# Core_Board_FPGA_STM32.net
KiCad netlist of a schematic drawn in Altium Designer
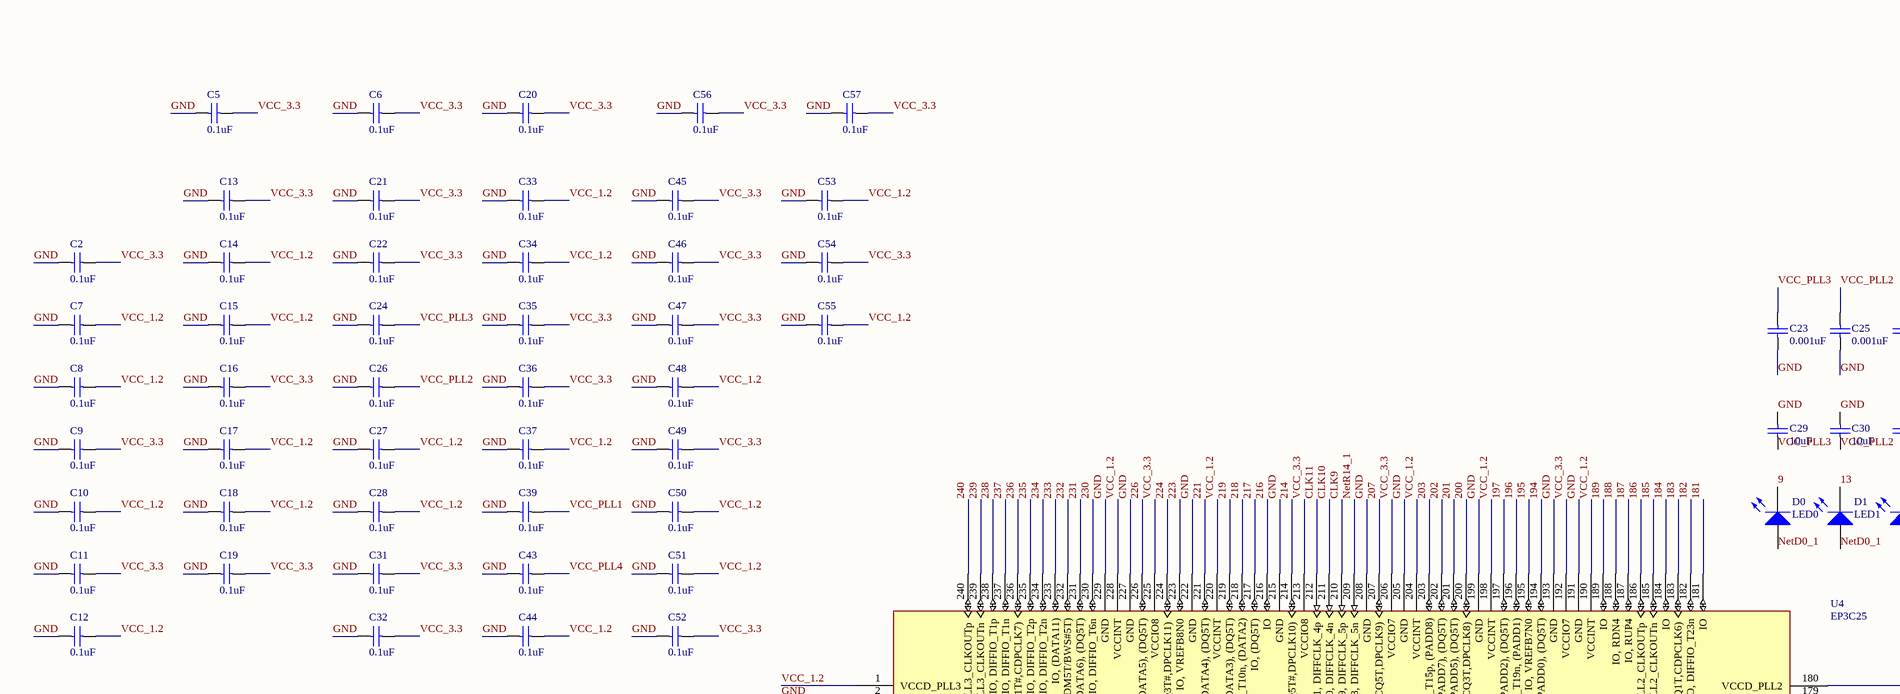
[diagram p0: Core_Board_FPGA_STM32.SchDoc, top left]
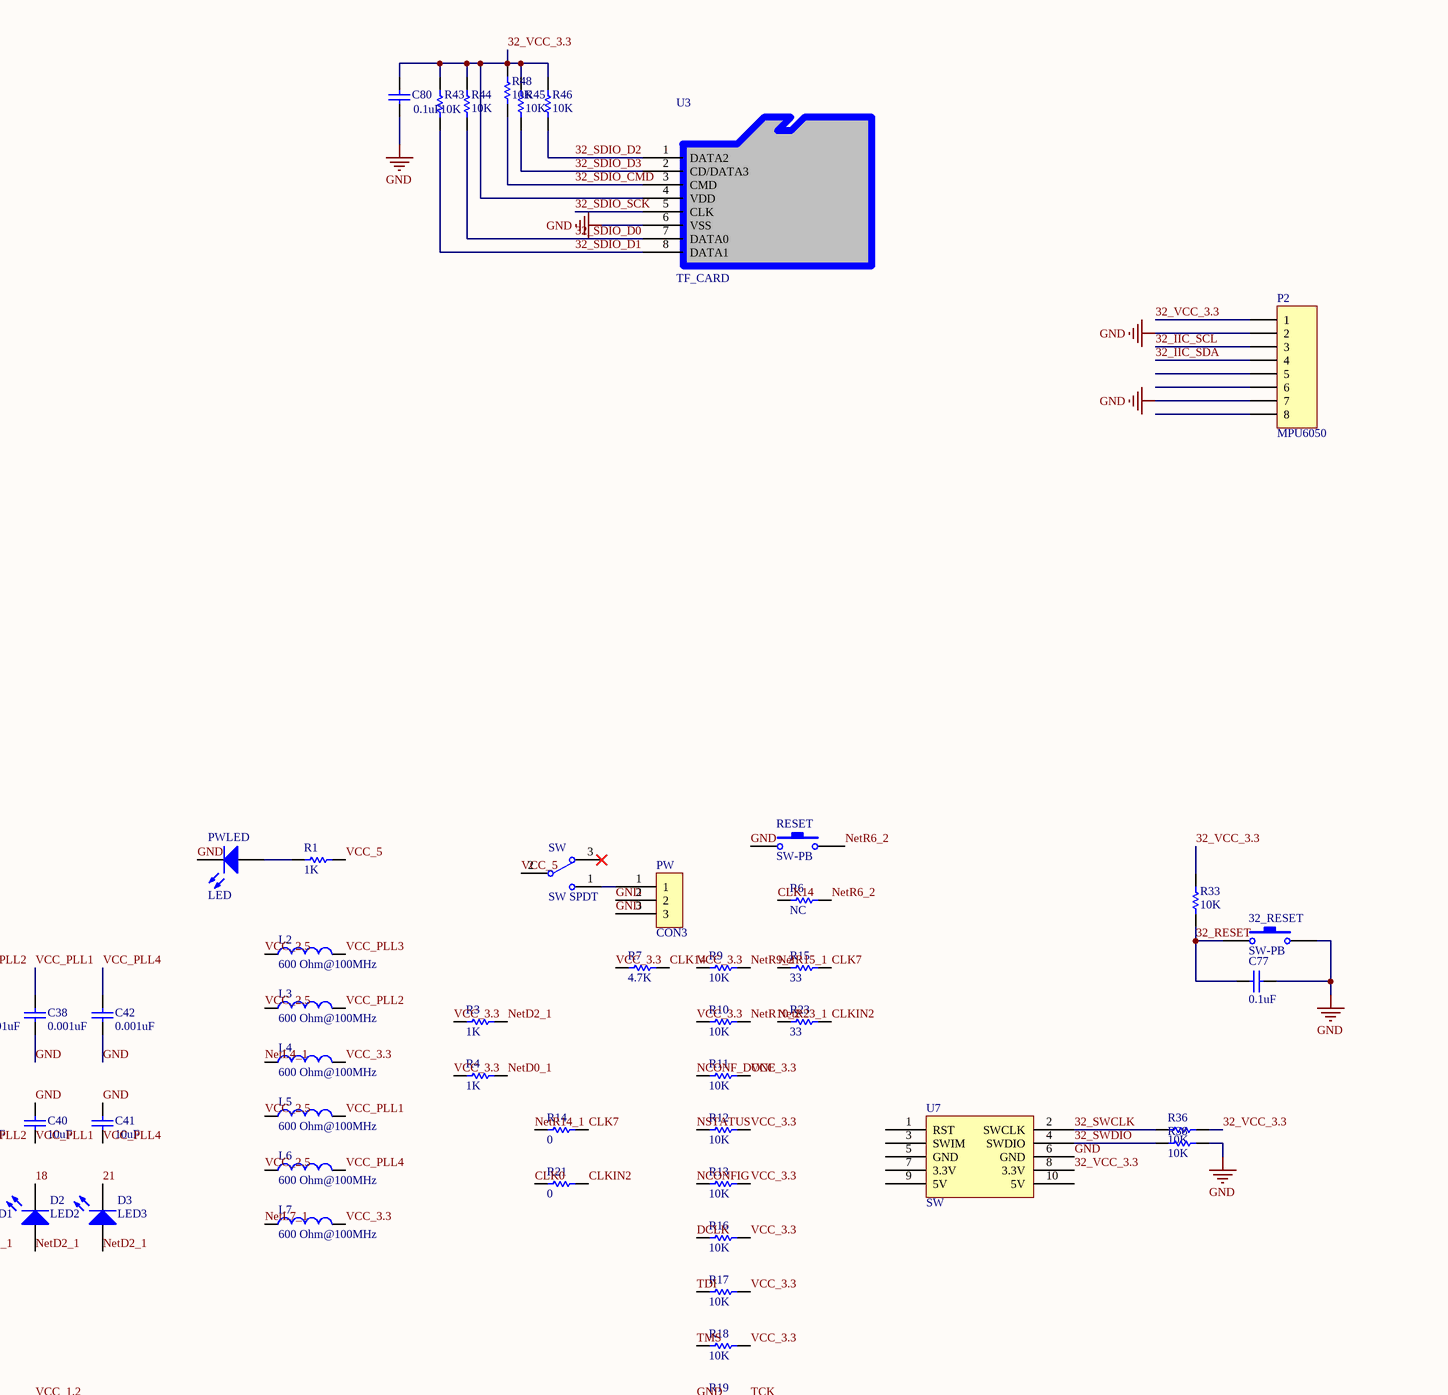
[diagram p1: Core_Board_FPGA_STM32.SchDoc, top middle]
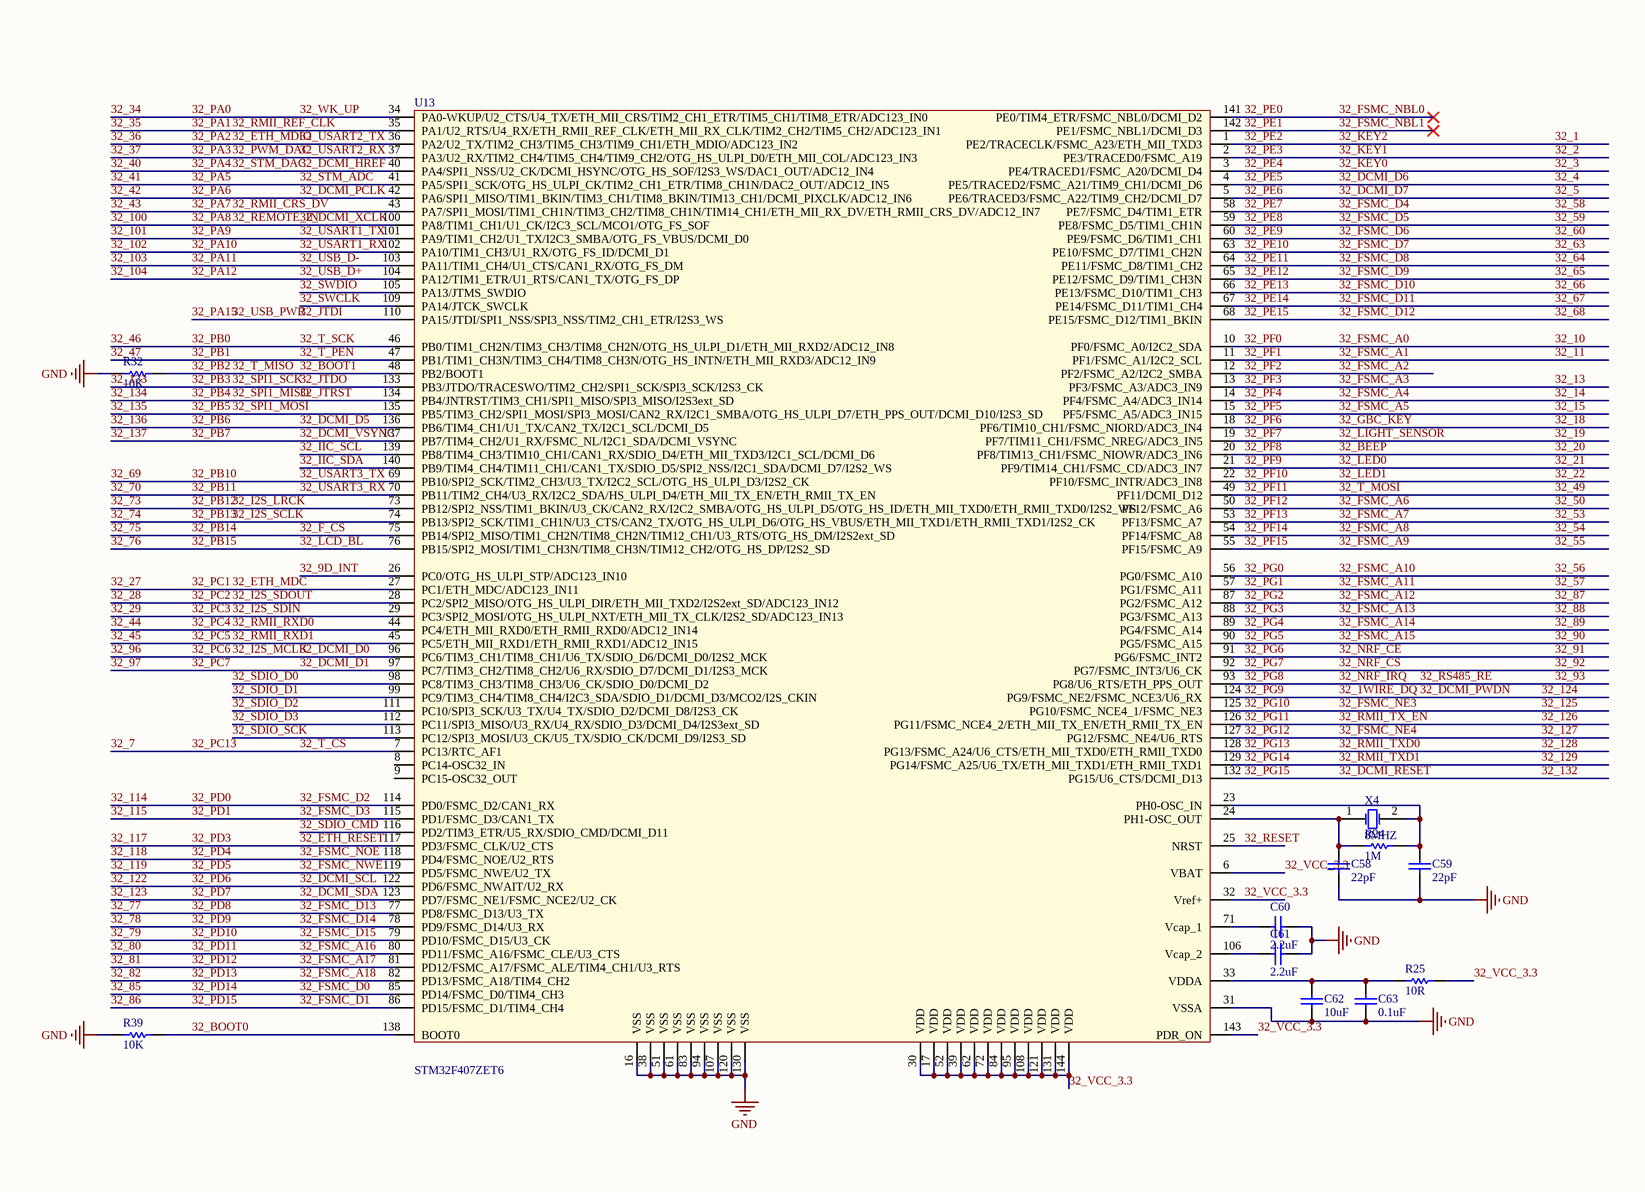
[diagram p2: Core_Board_FPGA_STM32.SchDoc, top right]
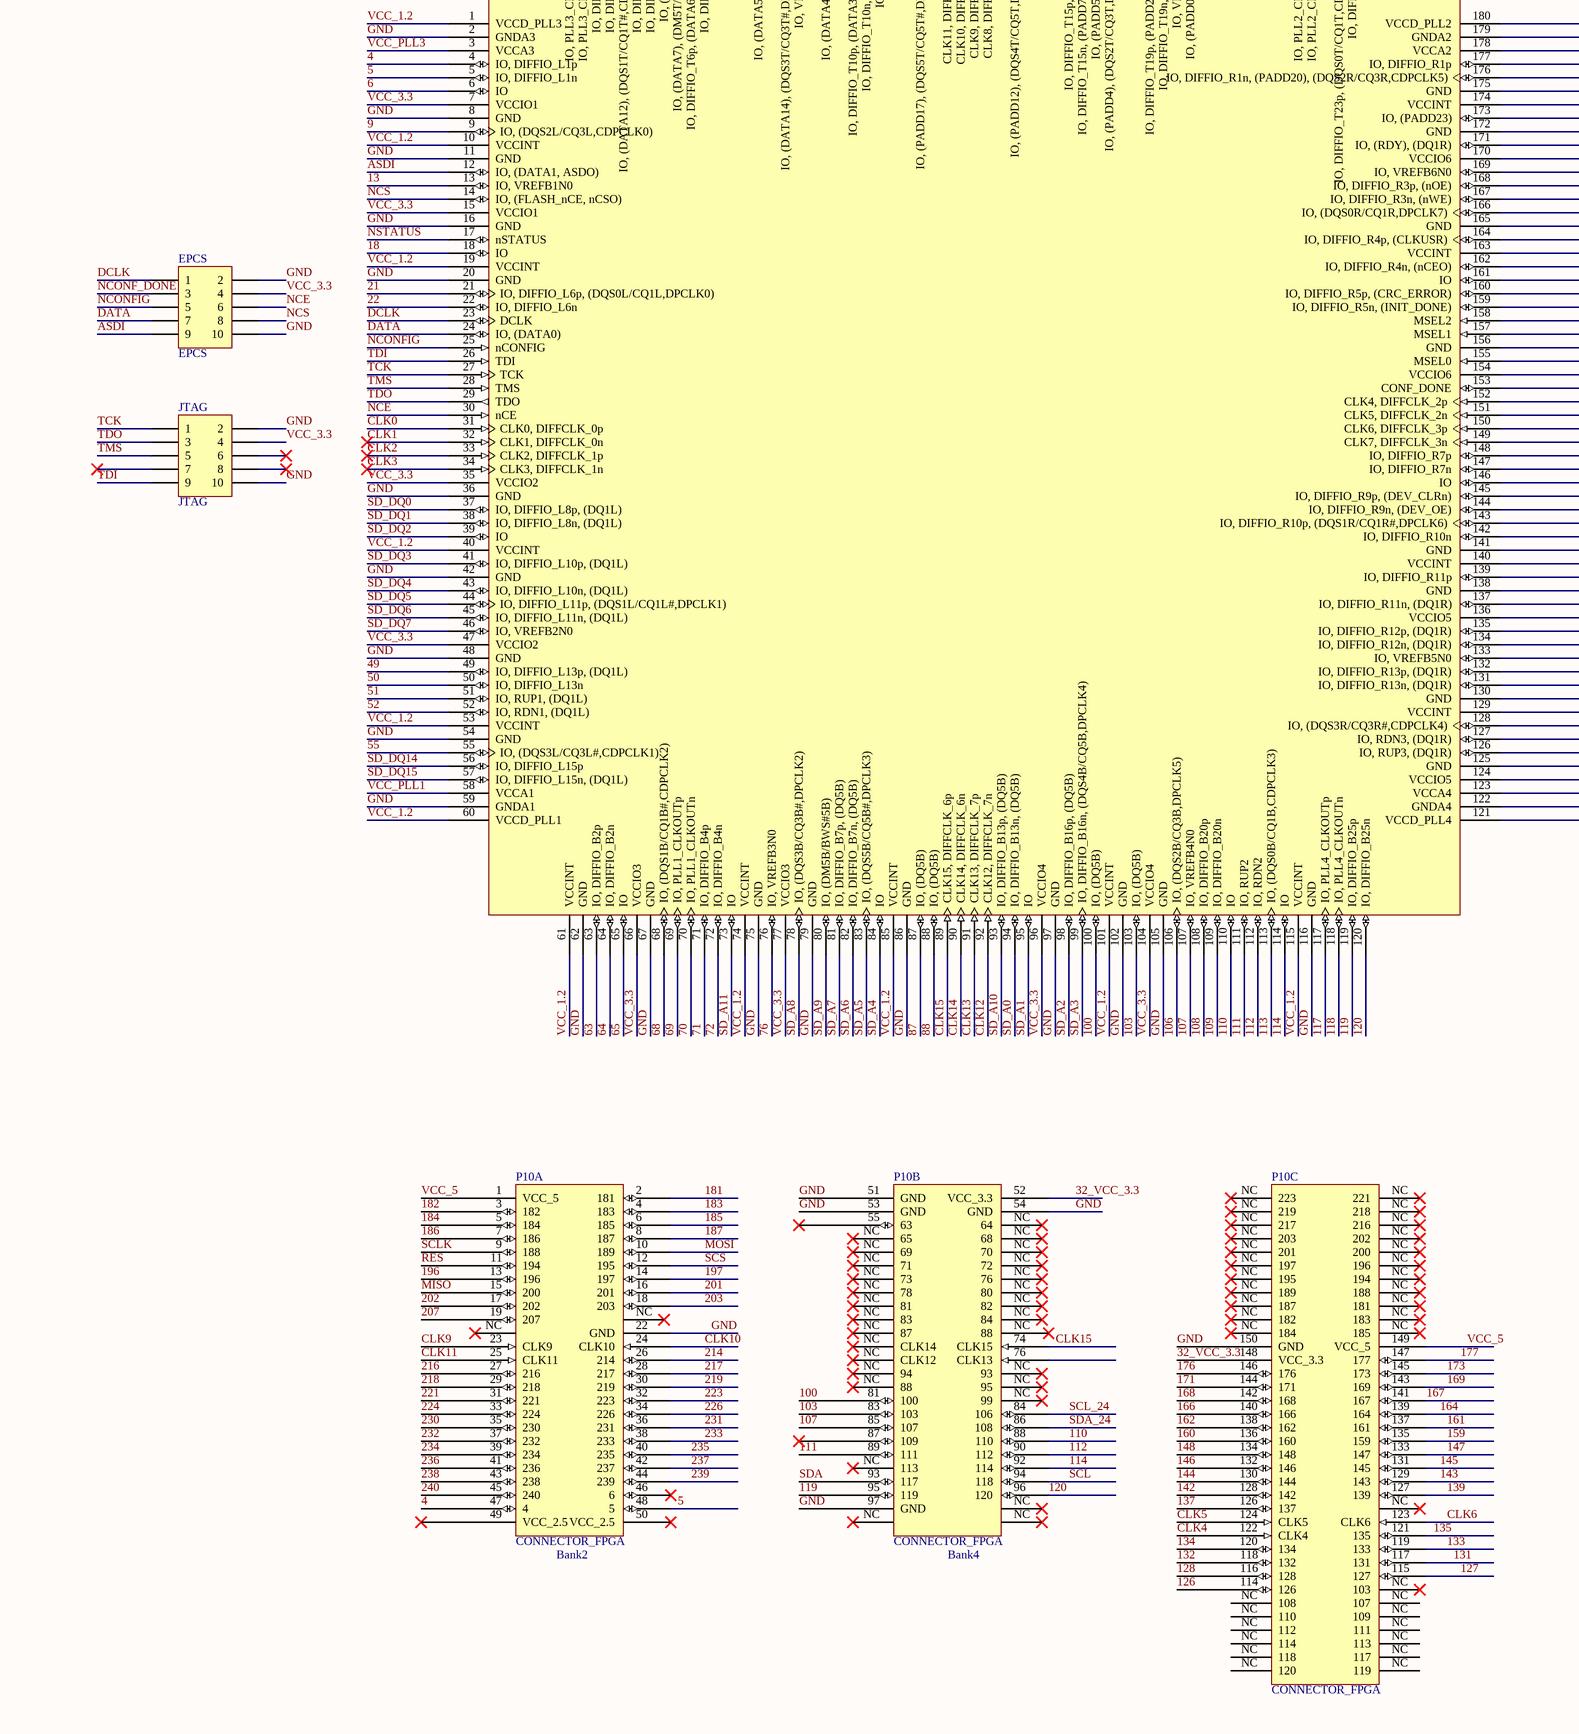
[diagram p3: Core_Board_FPGA_STM32.SchDoc, bottom left]
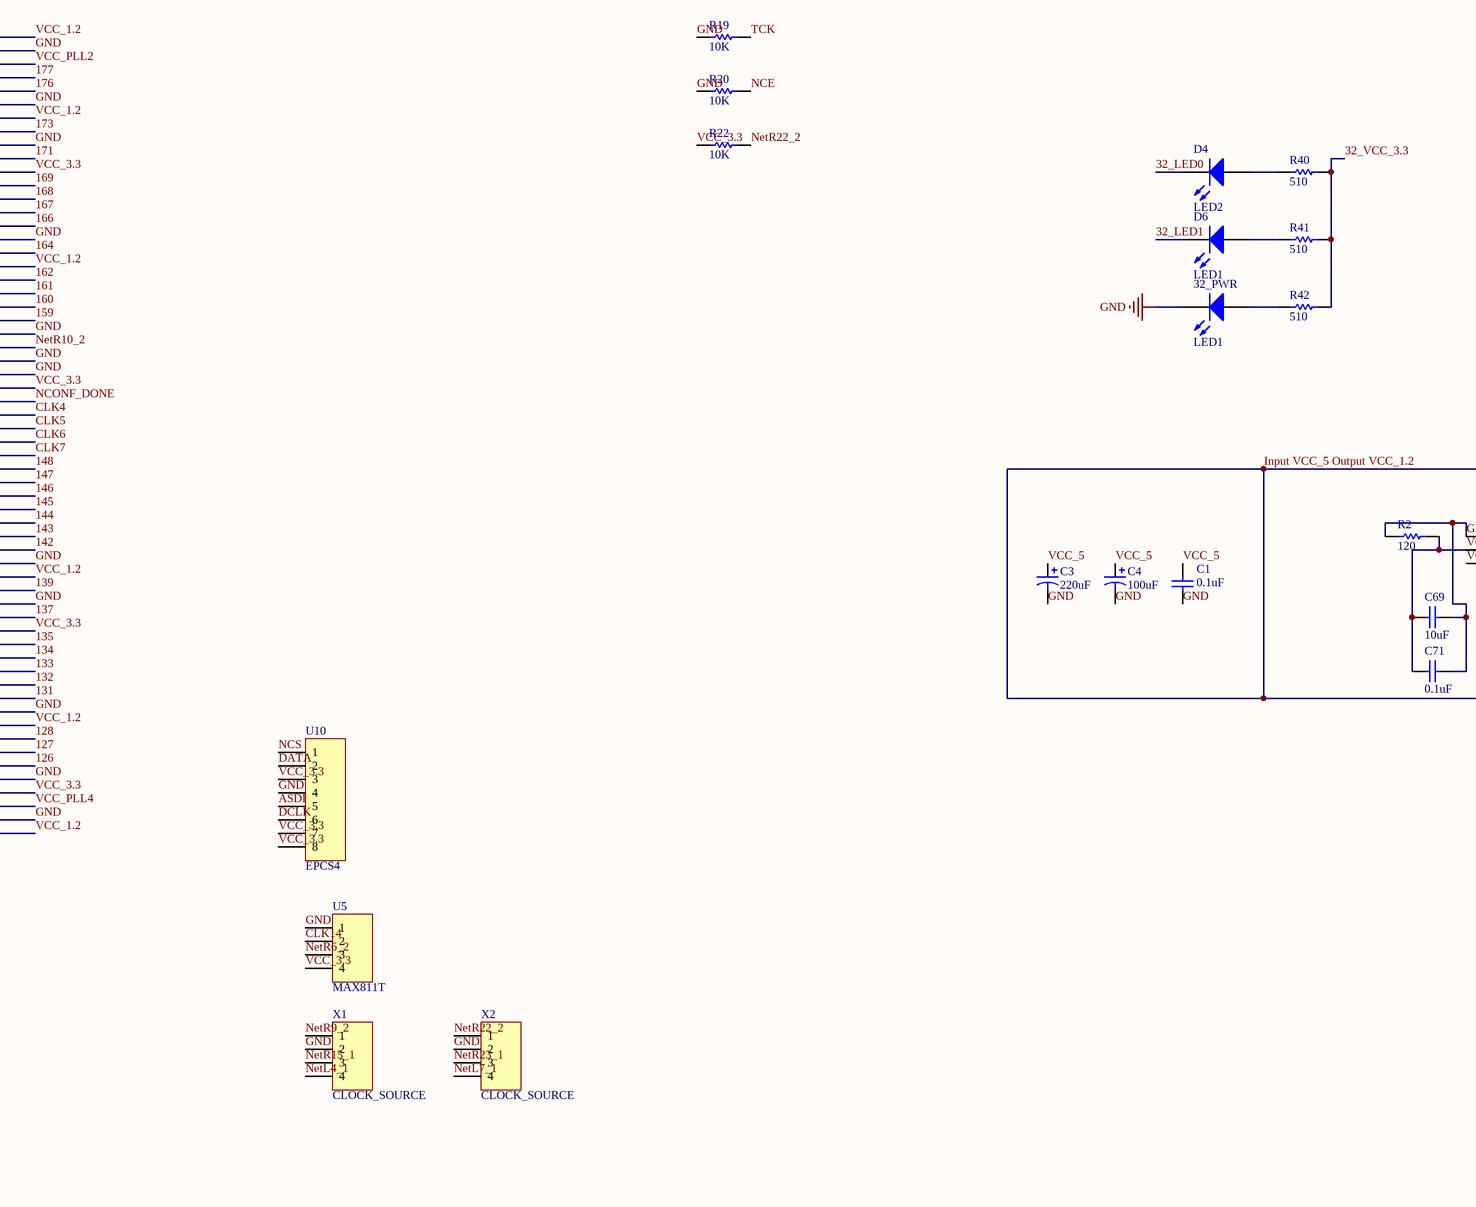
[diagram p4: Core_Board_FPGA_STM32.SchDoc, bottom middle]
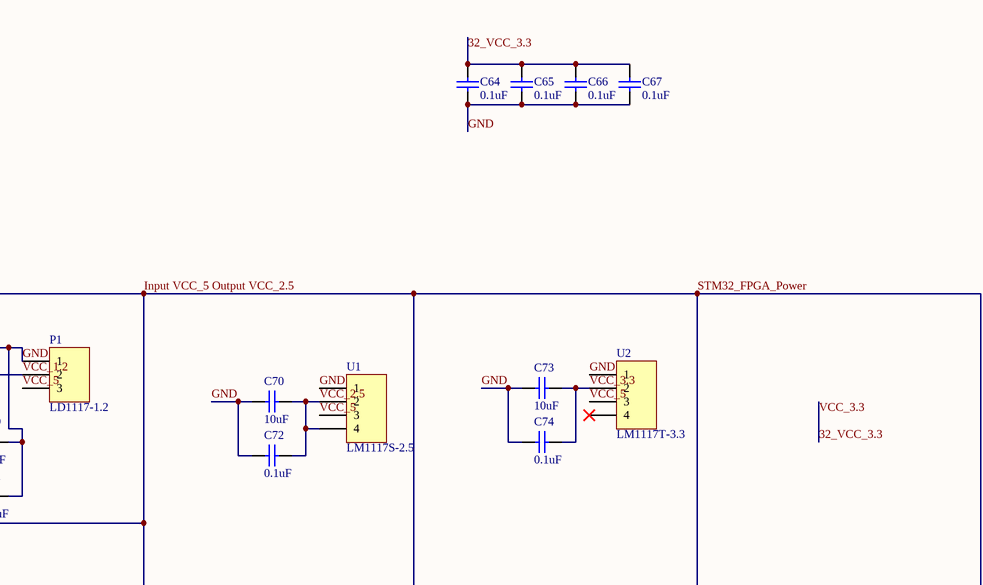
[diagram p5: Core_Board_FPGA_STM32.SchDoc, bottom right]

(export (version "E")
  (design (tool "Eeschema 10.0.6"))
  (components
    (comp (ref "32_PWR")
      (value "LED1")
      (footprint "0805D")
      (description "Typical INFRARED GaAs LED")
      (fields (field (name "PUBLISHER") "Altium Limited"))
      (libsource (lib "Miscellaneous Devices") (part "LED0"))
    )
    (comp (ref "32_RESET")
      (value "SW-PB")
      (footprint "SMD_SWITH")
      (description "Switch")
      (fields (field (name "PUBLISHER") "Altium Limited"))
      (libsource (lib "Miscellaneous Devices") (part "SW-PB"))
    )
    (comp (ref "C1")
      (value "0.1uF")
      (footprint "0805C")
      (description "Capacitor")
      (fields (field (name "PUBLISHER") "Altium Limited"))
      (libsource (lib "Miscellaneous Devices") (part "Cap"))
    )
    (comp (ref "C2")
      (value "0.1uF")
      (footprint "0805C")
      (description "Capacitor")
      (fields (field (name "PUBLISHER") "Altium Limited"))
      (libsource (lib "Miscellaneous Devices") (part "Cap"))
    )
    (comp (ref "C3")
      (value "220uF")
      (footprint "Cap6.6*6.6")
      (description "Polarized Capacitor (Radial)")
      (fields (field (name "PUBLISHER") "Altium Limited"))
      (libsource (lib "Miscellaneous Devices") (part "Cap Pol1"))
    )
    (comp (ref "C4")
      (value "100uF")
      (footprint "Cap6.6*6.6")
      (description "Polarized Capacitor (Radial)")
      (fields (field (name "PUBLISHER") "Altium Limited"))
      (libsource (lib "Miscellaneous Devices") (part "Cap Pol1"))
    )
    (comp (ref "C5")
      (value "0.1uF")
      (footprint "0805C")
      (description "Capacitor")
      (fields (field (name "PUBLISHER") "Altium Limited"))
      (libsource (lib "Miscellaneous Devices") (part "Cap"))
    )
    (comp (ref "C6")
      (value "0.1uF")
      (footprint "0805C")
      (description "Capacitor")
      (fields (field (name "PUBLISHER") "Altium Limited"))
      (libsource (lib "Miscellaneous Devices") (part "Cap"))
    )
    (comp (ref "C7")
      (value "0.1uF")
      (footprint "0805C")
      (description "Capacitor")
      (fields (field (name "PUBLISHER") "Altium Limited"))
      (libsource (lib "Miscellaneous Devices") (part "Cap"))
    )
    (comp (ref "C8")
      (value "0.1uF")
      (footprint "0805C")
      (description "Capacitor")
      (fields (field (name "PUBLISHER") "Altium Limited"))
      (libsource (lib "Miscellaneous Devices") (part "Cap"))
    )
    (comp (ref "C9")
      (value "0.1uF")
      (footprint "0805C")
      (description "Capacitor")
      (fields (field (name "PUBLISHER") "Altium Limited"))
      (libsource (lib "Miscellaneous Devices") (part "Cap"))
    )
    (comp (ref "C10")
      (value "0.1uF")
      (footprint "0805C")
      (description "Capacitor")
      (fields (field (name "PUBLISHER") "Altium Limited"))
      (libsource (lib "Miscellaneous Devices") (part "Cap"))
    )
    (comp (ref "C11")
      (value "0.1uF")
      (footprint "0805C")
      (description "Capacitor")
      (fields (field (name "PUBLISHER") "Altium Limited"))
      (libsource (lib "Miscellaneous Devices") (part "Cap"))
    )
    (comp (ref "C12")
      (value "0.1uF")
      (footprint "0805C")
      (description "Capacitor")
      (fields (field (name "PUBLISHER") "Altium Limited"))
      (libsource (lib "Miscellaneous Devices") (part "Cap"))
    )
    (comp (ref "C13")
      (value "0.1uF")
      (footprint "0805C")
      (description "Capacitor")
      (fields (field (name "PUBLISHER") "Altium Limited"))
      (libsource (lib "Miscellaneous Devices") (part "Cap"))
    )
    (comp (ref "C14")
      (value "0.1uF")
      (footprint "0805C")
      (description "Capacitor")
      (fields (field (name "PUBLISHER") "Altium Limited"))
      (libsource (lib "Miscellaneous Devices") (part "Cap"))
    )
    (comp (ref "C15")
      (value "0.1uF")
      (footprint "0805C")
      (description "Capacitor")
      (fields (field (name "PUBLISHER") "Altium Limited"))
      (libsource (lib "Miscellaneous Devices") (part "Cap"))
    )
    (comp (ref "C16")
      (value "0.1uF")
      (footprint "0805C")
      (description "Capacitor")
      (fields (field (name "PUBLISHER") "Altium Limited"))
      (libsource (lib "Miscellaneous Devices") (part "Cap"))
    )
    (comp (ref "C17")
      (value "0.1uF")
      (footprint "0805C")
      (description "Capacitor")
      (fields (field (name "PUBLISHER") "Altium Limited"))
      (libsource (lib "Miscellaneous Devices") (part "Cap"))
    )
    (comp (ref "C18")
      (value "0.1uF")
      (footprint "0805C")
      (description "Capacitor")
      (fields (field (name "PUBLISHER") "Altium Limited"))
      (libsource (lib "Miscellaneous Devices") (part "Cap"))
    )
    (comp (ref "C19")
      (value "0.1uF")
      (footprint "0805C")
      (description "Capacitor")
      (fields (field (name "PUBLISHER") "Altium Limited"))
      (libsource (lib "Miscellaneous Devices") (part "Cap"))
    )
    (comp (ref "C20")
      (value "0.1uF")
      (footprint "0805C")
      (description "Capacitor")
      (fields (field (name "PUBLISHER") "Altium Limited"))
      (libsource (lib "Miscellaneous Devices") (part "Cap"))
    )
    (comp (ref "C21")
      (value "0.1uF")
      (footprint "0805C")
      (description "Capacitor")
      (fields (field (name "PUBLISHER") "Altium Limited"))
      (libsource (lib "Miscellaneous Devices") (part "Cap"))
    )
    (comp (ref "C22")
      (value "0.1uF")
      (footprint "0805C")
      (description "Capacitor")
      (fields (field (name "PUBLISHER") "Altium Limited"))
      (libsource (lib "Miscellaneous Devices") (part "Cap"))
    )
    (comp (ref "C23")
      (value "0.001uF")
      (footprint "0805C")
      (description "Capacitor")
      (fields (field (name "PUBLISHER") "Altium Limited"))
      (libsource (lib "Miscellaneous Devices") (part "Cap"))
    )
    (comp (ref "C24")
      (value "0.1uF")
      (footprint "0805C")
      (description "Capacitor")
      (fields (field (name "PUBLISHER") "Altium Limited"))
      (libsource (lib "Miscellaneous Devices") (part "Cap"))
    )
    (comp (ref "C25")
      (value "0.001uF")
      (footprint "0805C")
      (description "Capacitor")
      (fields (field (name "PUBLISHER") "Altium Limited"))
      (libsource (lib "Miscellaneous Devices") (part "Cap"))
    )
    (comp (ref "C26")
      (value "0.1uF")
      (footprint "0805C")
      (description "Capacitor")
      (fields (field (name "PUBLISHER") "Altium Limited"))
      (libsource (lib "Miscellaneous Devices") (part "Cap"))
    )
    (comp (ref "C27")
      (value "0.1uF")
      (footprint "0805C")
      (description "Capacitor")
      (fields (field (name "PUBLISHER") "Altium Limited"))
      (libsource (lib "Miscellaneous Devices") (part "Cap"))
    )
    (comp (ref "C28")
      (value "0.1uF")
      (footprint "0805C")
      (description "Capacitor")
      (fields (field (name "PUBLISHER") "Altium Limited"))
      (libsource (lib "Miscellaneous Devices") (part "Cap"))
    )
    (comp (ref "C29")
      (value "10uF")
      (footprint "0805C")
      (description "Capacitor")
      (fields (field (name "PUBLISHER") "Altium Limited"))
      (libsource (lib "Miscellaneous Devices") (part "Cap"))
    )
    (comp (ref "C30")
      (value "10uF")
      (footprint "0805C")
      (description "Capacitor")
      (fields (field (name "PUBLISHER") "Altium Limited"))
      (libsource (lib "Miscellaneous Devices") (part "Cap"))
    )
    (comp (ref "C31")
      (value "0.1uF")
      (footprint "0805C")
      (description "Capacitor")
      (fields (field (name "PUBLISHER") "Altium Limited"))
      (libsource (lib "Miscellaneous Devices") (part "Cap"))
    )
    (comp (ref "C32")
      (value "0.1uF")
      (footprint "0805C")
      (description "Capacitor")
      (fields (field (name "PUBLISHER") "Altium Limited"))
      (libsource (lib "Miscellaneous Devices") (part "Cap"))
    )
    (comp (ref "C33")
      (value "0.1uF")
      (footprint "0805C")
      (description "Capacitor")
      (fields (field (name "PUBLISHER") "Altium Limited"))
      (libsource (lib "Miscellaneous Devices") (part "Cap"))
    )
    (comp (ref "C34")
      (value "0.1uF")
      (footprint "0805C")
      (description "Capacitor")
      (fields (field (name "PUBLISHER") "Altium Limited"))
      (libsource (lib "Miscellaneous Devices") (part "Cap"))
    )
    (comp (ref "C35")
      (value "0.1uF")
      (footprint "0805C")
      (description "Capacitor")
      (fields (field (name "PUBLISHER") "Altium Limited"))
      (libsource (lib "Miscellaneous Devices") (part "Cap"))
    )
    (comp (ref "C36")
      (value "0.1uF")
      (footprint "0805C")
      (description "Capacitor")
      (fields (field (name "PUBLISHER") "Altium Limited"))
      (libsource (lib "Miscellaneous Devices") (part "Cap"))
    )
    (comp (ref "C37")
      (value "0.1uF")
      (footprint "0805C")
      (description "Capacitor")
      (fields (field (name "PUBLISHER") "Altium Limited"))
      (libsource (lib "Miscellaneous Devices") (part "Cap"))
    )
    (comp (ref "C38")
      (value "0.001uF")
      (footprint "0805C")
      (description "Capacitor")
      (fields (field (name "PUBLISHER") "Altium Limited"))
      (libsource (lib "Miscellaneous Devices") (part "Cap"))
    )
    (comp (ref "C39")
      (value "0.1uF")
      (footprint "0805C")
      (description "Capacitor")
      (fields (field (name "PUBLISHER") "Altium Limited"))
      (libsource (lib "Miscellaneous Devices") (part "Cap"))
    )
    (comp (ref "C40")
      (value "10uF")
      (footprint "0805C")
      (description "Capacitor")
      (fields (field (name "PUBLISHER") "Altium Limited"))
      (libsource (lib "Miscellaneous Devices") (part "Cap"))
    )
    (comp (ref "C41")
      (value "10uF")
      (footprint "0805C")
      (description "Capacitor")
      (fields (field (name "PUBLISHER") "Altium Limited"))
      (libsource (lib "Miscellaneous Devices") (part "Cap"))
    )
    (comp (ref "C42")
      (value "0.001uF")
      (footprint "0805C")
      (description "Capacitor")
      (fields (field (name "PUBLISHER") "Altium Limited"))
      (libsource (lib "Miscellaneous Devices") (part "Cap"))
    )
    (comp (ref "C43")
      (value "0.1uF")
      (footprint "0805C")
      (description "Capacitor")
      (fields (field (name "PUBLISHER") "Altium Limited"))
      (libsource (lib "Miscellaneous Devices") (part "Cap"))
    )
    (comp (ref "C44")
      (value "0.1uF")
      (footprint "0805C")
      (description "Capacitor")
      (fields (field (name "PUBLISHER") "Altium Limited"))
      (libsource (lib "Miscellaneous Devices") (part "Cap"))
    )
    (comp (ref "C45")
      (value "0.1uF")
      (footprint "0805C")
      (description "Capacitor")
      (fields (field (name "PUBLISHER") "Altium Limited"))
      (libsource (lib "Miscellaneous Devices") (part "Cap"))
    )
    (comp (ref "C46")
      (value "0.1uF")
      (footprint "0805C")
      (description "Capacitor")
      (fields (field (name "PUBLISHER") "Altium Limited"))
      (libsource (lib "Miscellaneous Devices") (part "Cap"))
    )
    (comp (ref "C47")
      (value "0.1uF")
      (footprint "0805C")
      (description "Capacitor")
      (fields (field (name "PUBLISHER") "Altium Limited"))
      (libsource (lib "Miscellaneous Devices") (part "Cap"))
    )
    (comp (ref "C48")
      (value "0.1uF")
      (footprint "0805C")
      (description "Capacitor")
      (fields (field (name "PUBLISHER") "Altium Limited"))
      (libsource (lib "Miscellaneous Devices") (part "Cap"))
    )
    (comp (ref "C49")
      (value "0.1uF")
      (footprint "0805C")
      (description "Capacitor")
      (fields (field (name "PUBLISHER") "Altium Limited"))
      (libsource (lib "Miscellaneous Devices") (part "Cap"))
    )
    (comp (ref "C50")
      (value "0.1uF")
      (footprint "0805C")
      (description "Capacitor")
      (fields (field (name "PUBLISHER") "Altium Limited"))
      (libsource (lib "Miscellaneous Devices") (part "Cap"))
    )
    (comp (ref "C51")
      (value "0.1uF")
      (footprint "0805C")
      (description "Capacitor")
      (fields (field (name "PUBLISHER") "Altium Limited"))
      (libsource (lib "Miscellaneous Devices") (part "Cap"))
    )
    (comp (ref "C52")
      (value "0.1uF")
      (footprint "0805C")
      (description "Capacitor")
      (fields (field (name "PUBLISHER") "Altium Limited"))
      (libsource (lib "Miscellaneous Devices") (part "Cap"))
    )
    (comp (ref "C53")
      (value "0.1uF")
      (footprint "0805C")
      (description "Capacitor")
      (fields (field (name "PUBLISHER") "Altium Limited"))
      (libsource (lib "Miscellaneous Devices") (part "Cap"))
    )
    (comp (ref "C54")
      (value "0.1uF")
      (footprint "0805C")
      (description "Capacitor")
      (fields (field (name "PUBLISHER") "Altium Limited"))
      (libsource (lib "Miscellaneous Devices") (part "Cap"))
    )
    (comp (ref "C55")
      (value "0.1uF")
      (footprint "0805C")
      (description "Capacitor")
      (fields (field (name "PUBLISHER") "Altium Limited"))
      (libsource (lib "Miscellaneous Devices") (part "Cap"))
    )
    (comp (ref "C56")
      (value "0.1uF")
      (footprint "0805C")
      (description "Capacitor")
      (fields (field (name "PUBLISHER") "Altium Limited"))
      (libsource (lib "Miscellaneous Devices") (part "Cap"))
    )
    (comp (ref "C57")
      (value "0.1uF")
      (footprint "0805C")
      (description "Capacitor")
      (fields (field (name "PUBLISHER") "Altium Limited"))
      (libsource (lib "Miscellaneous Devices") (part "Cap"))
    )
    (comp (ref "C58")
      (value "22pF")
      (footprint "0805C")
      (description "Capacitor")
      (fields (field (name "PUBLISHER") "Altium Limited"))
      (libsource (lib "Miscellaneous Devices") (part "Cap"))
    )
    (comp (ref "C59")
      (value "22pF")
      (footprint "0805C")
      (description "Capacitor")
      (fields (field (name "PUBLISHER") "Altium Limited"))
      (libsource (lib "Miscellaneous Devices") (part "Cap"))
    )
    (comp (ref "C60")
      (value "2.2uF")
      (footprint "0805C")
      (description "Capacitor")
      (fields (field (name "PUBLISHER") "Altium Limited"))
      (libsource (lib "Miscellaneous Devices") (part "Cap"))
    )
    (comp (ref "C61")
      (value "2.2uF")
      (footprint "0805C")
      (description "Capacitor")
      (fields (field (name "PUBLISHER") "Altium Limited"))
      (libsource (lib "Miscellaneous Devices") (part "Cap"))
    )
    (comp (ref "C62")
      (value "10uF")
      (footprint "0805C")
      (description "Capacitor")
      (fields (field (name "PUBLISHER") "Altium Limited"))
      (libsource (lib "Miscellaneous Devices") (part "Cap"))
    )
    (comp (ref "C63")
      (value "0.1uF")
      (footprint "0805C")
      (description "Capacitor")
      (fields (field (name "PUBLISHER") "Altium Limited"))
      (libsource (lib "Miscellaneous Devices") (part "Cap"))
    )
    (comp (ref "C64")
      (value "0.1uF")
      (footprint "0805C")
      (description "Capacitor")
      (fields (field (name "PUBLISHER") "Altium Limited"))
      (libsource (lib "Miscellaneous Devices") (part "Cap"))
    )
    (comp (ref "C65")
      (value "0.1uF")
      (footprint "0805C")
      (description "Capacitor")
      (fields (field (name "PUBLISHER") "Altium Limited"))
      (libsource (lib "Miscellaneous Devices") (part "Cap"))
    )
    (comp (ref "C66")
      (value "0.1uF")
      (footprint "0805C")
      (description "Capacitor")
      (fields (field (name "PUBLISHER") "Altium Limited"))
      (libsource (lib "Miscellaneous Devices") (part "Cap"))
    )
    (comp (ref "C67")
      (value "0.1uF")
      (footprint "0805C")
      (description "Capacitor")
      (fields (field (name "PUBLISHER") "Altium Limited"))
      (libsource (lib "Miscellaneous Devices") (part "Cap"))
    )
    (comp (ref "C69")
      (value "10uF")
      (footprint "0805C")
      (description "Capacitor")
      (fields (field (name "PUBLISHER") "Altium Limited"))
      (libsource (lib "Miscellaneous Devices") (part "Cap"))
    )
    (comp (ref "C70")
      (value "10uF")
      (footprint "0805C")
      (description "Capacitor")
      (fields (field (name "PUBLISHER") "Altium Limited"))
      (libsource (lib "Miscellaneous Devices") (part "Cap"))
    )
    (comp (ref "C71")
      (value "0.1uF")
      (footprint "0805C")
      (description "Capacitor")
      (fields (field (name "PUBLISHER") "Altium Limited"))
      (libsource (lib "Miscellaneous Devices") (part "Cap"))
    )
    (comp (ref "C72")
      (value "0.1uF")
      (footprint "0805C")
      (description "Capacitor")
      (fields (field (name "PUBLISHER") "Altium Limited"))
      (libsource (lib "Miscellaneous Devices") (part "Cap"))
    )
    (comp (ref "C73")
      (value "10uF")
      (footprint "0805C")
      (description "Capacitor")
      (fields (field (name "PUBLISHER") "Altium Limited"))
      (libsource (lib "Miscellaneous Devices") (part "Cap"))
    )
    (comp (ref "C74")
      (value "0.1uF")
      (footprint "0805C")
      (description "Capacitor")
      (fields (field (name "PUBLISHER") "Altium Limited"))
      (libsource (lib "Miscellaneous Devices") (part "Cap"))
    )
    (comp (ref "C77")
      (value "0.1uF")
      (footprint "0805C")
      (description "Capacitor")
      (fields (field (name "PUBLISHER") "Altium Limited"))
      (libsource (lib "Miscellaneous Devices") (part "Cap"))
    )
    (comp (ref "C80")
      (value "0.1uF")
      (footprint "0805C")
      (description "Capacitor")
      (fields (field (name "PUBLISHER") "Altium Limited"))
      (libsource (lib "Miscellaneous Devices") (part "Cap"))
    )
    (comp (ref "D0")
      (value "LED0")
      (footprint "0805D")
      (description "Typical INFRARED GaAs LED")
      (fields (field (name "PUBLISHER") "Altium Limited"))
      (libsource (lib "Miscellaneous Devices") (part "LED0"))
    )
    (comp (ref "D1")
      (value "LED1")
      (footprint "0805D")
      (description "Typical INFRARED GaAs LED")
      (fields (field (name "PUBLISHER") "Altium Limited"))
      (libsource (lib "Miscellaneous Devices") (part "LED0"))
    )
    (comp (ref "D2")
      (value "LED2")
      (footprint "0805D")
      (description "Typical INFRARED GaAs LED")
      (fields (field (name "PUBLISHER") "Altium Limited"))
      (libsource (lib "Miscellaneous Devices") (part "LED0"))
    )
    (comp (ref "D3")
      (value "LED3")
      (footprint "0805D")
      (description "Typical INFRARED GaAs LED")
      (fields (field (name "PUBLISHER") "Altium Limited"))
      (libsource (lib "Miscellaneous Devices") (part "LED0"))
    )
    (comp (ref "D4")
      (value "LED2")
      (footprint "0805D")
      (description "Typical INFRARED GaAs LED")
      (fields (field (name "PUBLISHER") "Altium Limited"))
      (libsource (lib "Miscellaneous Devices") (part "LED0"))
    )
    (comp (ref "D6")
      (value "LED1")
      (footprint "0805D")
      (description "Typical INFRARED GaAs LED")
      (fields (field (name "PUBLISHER") "Altium Limited"))
      (libsource (lib "Miscellaneous Devices") (part "LED0"))
    )
    (comp (ref "EPCS")
      (value "EPCS")
      (footprint "IDC10_S")
      (description "Header, 5-Pin, Dual row")
      (fields (field (name "PUBLISHER") "Altium Limited"))
      (libsource (lib "Miscellaneous Connectors") (part "Header 5X2"))
    )
    (comp (ref "JTAG")
      (value "JTAG")
      (footprint "IDC10_S")
      (description "Header, 5-Pin, Dual row")
      (fields (field (name "PUBLISHER") "Altium Limited"))
      (libsource (lib "Miscellaneous Connectors") (part "Header 5X2"))
    )
    (comp (ref "L2")
      (value "600 Ohm@100MHz")
      (footprint "0805R")
      (description "Inductor")
      (fields (field (name "PUBLISHER") "Altium Limited"))
      (libsource (lib "Miscellaneous Devices") (part "Inductor"))
    )
    (comp (ref "L3")
      (value "600 Ohm@100MHz")
      (footprint "0805R")
      (description "Inductor")
      (fields (field (name "PUBLISHER") "Altium Limited"))
      (libsource (lib "Miscellaneous Devices") (part "Inductor"))
    )
    (comp (ref "L4")
      (value "600 Ohm@100MHz")
      (footprint "0805R")
      (description "Inductor")
      (fields (field (name "PUBLISHER") "Altium Limited"))
      (libsource (lib "Miscellaneous Devices") (part "Inductor"))
    )
    (comp (ref "L5")
      (value "600 Ohm@100MHz")
      (footprint "0805R")
      (description "Inductor")
      (fields (field (name "PUBLISHER") "Altium Limited"))
      (libsource (lib "Miscellaneous Devices") (part "Inductor"))
    )
    (comp (ref "L6")
      (value "600 Ohm@100MHz")
      (footprint "0805R")
      (description "Inductor")
      (fields (field (name "PUBLISHER") "Altium Limited"))
      (libsource (lib "Miscellaneous Devices") (part "Inductor"))
    )
    (comp (ref "L7")
      (value "600 Ohm@100MHz")
      (footprint "0805R")
      (description "Inductor")
      (fields (field (name "PUBLISHER") "Altium Limited"))
      (libsource (lib "Miscellaneous Devices") (part "Inductor"))
    )
    (comp (ref "P1")
      (value "LD1117-1.2")
      (footprint "TO-252")
      (description "Header, 3-Pin")
      (fields (field (name "PUBLISHER") "Altium Limited"))
      (libsource (lib "Miscellaneous Connectors") (part "Header 3"))
    )
    (comp (ref "P2")
      (value "MPU6050")
      (footprint "HDR1X8")
      (description "Header, 8-Pin")
      (fields (field (name "PUBLISHER") "Altium Limited"))
      (libsource (lib "Miscellaneous Connectors") (part "Header 8"))
    )
    (comp (ref "P10")
      (value "CONNECTOR_FPGA")
      (footprint "CONNECTOR_FPGA")
      (libsource (lib "hp_2018_03") (part "CONNECTOR_FPGA"))
    )
    (comp (ref "PW") (value "CON3") (footprint "PW_PORT") (libsource (lib "EP3C25") (part "CON3")))
    (comp (ref "PWLED")
      (value "LED")
      (footprint "0805D")
      (description "Typical INFRARED GaAs LED")
      (fields (field (name "PUBLISHER") "Altium Limited"))
      (libsource (lib "Miscellaneous Devices") (part "LED0"))
    )
    (comp (ref "R1")
      (value "1K")
      (footprint "0805R")
      (description "Resistor")
      (fields (field (name "PUBLISHER") "Altium Limited"))
      (libsource (lib "Miscellaneous Devices") (part "Res1"))
    )
    (comp (ref "R2")
      (value "120")
      (footprint "0805R")
      (description "Resistor")
      (fields (field (name "PUBLISHER") "Altium Limited"))
      (libsource (lib "Miscellaneous Devices") (part "Res1"))
    )
    (comp (ref "R3")
      (value "1K")
      (footprint "0805R")
      (description "Resistor")
      (fields (field (name "PUBLISHER") "Altium Limited"))
      (libsource (lib "Miscellaneous Devices") (part "Res1"))
    )
    (comp (ref "R4")
      (value "1K")
      (footprint "0805R")
      (description "Resistor")
      (fields (field (name "PUBLISHER") "Altium Limited"))
      (libsource (lib "Miscellaneous Devices") (part "Res1"))
    )
    (comp (ref "R6")
      (value "NC")
      (footprint "0805R")
      (description "Resistor")
      (fields (field (name "PUBLISHER") "Altium Limited"))
      (libsource (lib "Miscellaneous Devices") (part "Res1"))
    )
    (comp (ref "R7")
      (value "4.7K")
      (footprint "0805R")
      (description "Resistor")
      (fields (field (name "PUBLISHER") "Altium Limited"))
      (libsource (lib "Miscellaneous Devices") (part "Res1"))
    )
    (comp (ref "R9")
      (value "10K")
      (footprint "0805R")
      (description "Resistor")
      (fields (field (name "PUBLISHER") "Altium Limited"))
      (libsource (lib "Miscellaneous Devices") (part "Res1"))
    )
    (comp (ref "R10")
      (value "10K")
      (footprint "0805R")
      (description "Resistor")
      (fields (field (name "PUBLISHER") "Altium Limited"))
      (libsource (lib "Miscellaneous Devices") (part "Res1"))
    )
    (comp (ref "R11")
      (value "10K")
      (footprint "0805R")
      (description "Resistor")
      (fields (field (name "PUBLISHER") "Altium Limited"))
      (libsource (lib "Miscellaneous Devices") (part "Res1"))
    )
    (comp (ref "R12")
      (value "10K")
      (footprint "0805R")
      (description "Resistor")
      (fields (field (name "PUBLISHER") "Altium Limited"))
      (libsource (lib "Miscellaneous Devices") (part "Res1"))
    )
    (comp (ref "R13")
      (value "10K")
      (footprint "0805R")
      (description "Resistor")
      (fields (field (name "PUBLISHER") "Altium Limited"))
      (libsource (lib "Miscellaneous Devices") (part "Res1"))
    )
    (comp (ref "R14")
      (value "0")
      (footprint "0805R")
      (description "Resistor")
      (fields (field (name "PUBLISHER") "Altium Limited"))
      (libsource (lib "Miscellaneous Devices") (part "Res1"))
    )
    (comp (ref "R15")
      (value "33")
      (footprint "0805R")
      (description "Resistor")
      (fields (field (name "PUBLISHER") "Altium Limited"))
      (libsource (lib "Miscellaneous Devices") (part "Res1"))
    )
    (comp (ref "R16")
      (value "10K")
      (footprint "0805R")
      (description "Resistor")
      (fields (field (name "PUBLISHER") "Altium Limited"))
      (libsource (lib "Miscellaneous Devices") (part "Res1"))
    )
    (comp (ref "R17")
      (value "10K")
      (footprint "0805R")
      (description "Resistor")
      (fields (field (name "PUBLISHER") "Altium Limited"))
      (libsource (lib "Miscellaneous Devices") (part "Res1"))
    )
    (comp (ref "R18")
      (value "10K")
      (footprint "0805R")
      (description "Resistor")
      (fields (field (name "PUBLISHER") "Altium Limited"))
      (libsource (lib "Miscellaneous Devices") (part "Res1"))
    )
    (comp (ref "R19")
      (value "10K")
      (footprint "0805R")
      (description "Resistor")
      (fields (field (name "PUBLISHER") "Altium Limited"))
      (libsource (lib "Miscellaneous Devices") (part "Res1"))
    )
    (comp (ref "R20")
      (value "10K")
      (footprint "0805R")
      (description "Resistor")
      (fields (field (name "PUBLISHER") "Altium Limited"))
      (libsource (lib "Miscellaneous Devices") (part "Res1"))
    )
    (comp (ref "R21")
      (value "0")
      (footprint "0805R")
      (description "Resistor")
      (fields (field (name "PUBLISHER") "Altium Limited"))
      (libsource (lib "Miscellaneous Devices") (part "Res1"))
    )
    (comp (ref "R22")
      (value "10K")
      (footprint "0805R")
      (description "Resistor")
      (fields (field (name "PUBLISHER") "Altium Limited"))
      (libsource (lib "Miscellaneous Devices") (part "Res1"))
    )
    (comp (ref "R23")
      (value "33")
      (footprint "0805R")
      (description "Resistor")
      (fields (field (name "PUBLISHER") "Altium Limited"))
      (libsource (lib "Miscellaneous Devices") (part "Res1"))
    )
    (comp (ref "R24")
      (value "1M")
      (footprint "0805R")
      (description "Resistor")
      (fields (field (name "PUBLISHER") "Altium Limited"))
      (libsource (lib "Miscellaneous Devices") (part "Res1"))
    )
    (comp (ref "R25")
      (value "10R")
      (footprint "0805R")
      (description "Resistor")
      (fields (field (name "PUBLISHER") "Altium Limited"))
      (libsource (lib "Miscellaneous Devices") (part "Res1"))
    )
    (comp (ref "R32")
      (value "10K")
      (footprint "0805R")
      (description "Resistor")
      (fields (field (name "PUBLISHER") "Altium Limited"))
      (libsource (lib "Miscellaneous Devices") (part "Res1"))
    )
    (comp (ref "R33")
      (value "10K")
      (footprint "0805R")
      (description "Resistor")
      (fields (field (name "PUBLISHER") "Altium Limited"))
      (libsource (lib "Miscellaneous Devices") (part "Res1"))
    )
    (comp (ref "R36")
      (value "10K")
      (footprint "0805R")
      (description "Resistor")
      (fields (field (name "PUBLISHER") "Altium Limited"))
      (libsource (lib "Miscellaneous Devices") (part "Res1"))
    )
    (comp (ref "R38")
      (value "10K")
      (footprint "0805R")
      (description "Resistor")
      (fields (field (name "PUBLISHER") "Altium Limited"))
      (libsource (lib "Miscellaneous Devices") (part "Res1"))
    )
    (comp (ref "R39")
      (value "10K")
      (footprint "0805R")
      (description "Resistor")
      (fields (field (name "PUBLISHER") "Altium Limited"))
      (libsource (lib "Miscellaneous Devices") (part "Res1"))
    )
    (comp (ref "R40")
      (value "510")
      (footprint "0805R")
      (description "Resistor")
      (fields (field (name "PUBLISHER") "Altium Limited"))
      (libsource (lib "Miscellaneous Devices") (part "Res1"))
    )
    (comp (ref "R41")
      (value "510")
      (footprint "0805R")
      (description "Resistor")
      (fields (field (name "PUBLISHER") "Altium Limited"))
      (libsource (lib "Miscellaneous Devices") (part "Res1"))
    )
    (comp (ref "R42")
      (value "510")
      (footprint "0805R")
      (description "Resistor")
      (fields (field (name "PUBLISHER") "Altium Limited"))
      (libsource (lib "Miscellaneous Devices") (part "Res1"))
    )
    (comp (ref "R43")
      (value "10K")
      (footprint "1608[0603R]")
      (description "Resistor")
      (fields (field (name "PUBLISHER") "Altium Limited"))
      (libsource (lib "Miscellaneous Devices") (part "Res1"))
    )
    (comp (ref "R44")
      (value "10K")
      (footprint "1608[0603R]")
      (description "Resistor")
      (fields (field (name "PUBLISHER") "Altium Limited"))
      (libsource (lib "Miscellaneous Devices") (part "Res1"))
    )
    (comp (ref "R45")
      (value "10K")
      (footprint "1608[0603R]")
      (description "Resistor")
      (fields (field (name "PUBLISHER") "Altium Limited"))
      (libsource (lib "Miscellaneous Devices") (part "Res1"))
    )
    (comp (ref "R46")
      (value "10K")
      (footprint "1608[0603R]")
      (description "Resistor")
      (fields (field (name "PUBLISHER") "Altium Limited"))
      (libsource (lib "Miscellaneous Devices") (part "Res1"))
    )
    (comp (ref "R48")
      (value "10K")
      (footprint "1608[0603R]")
      (description "Resistor")
      (fields (field (name "PUBLISHER") "Altium Limited"))
      (libsource (lib "Miscellaneous Devices") (part "Res1"))
    )
    (comp (ref "RESET")
      (value "SW-PB")
      (footprint "SMD_SWITH")
      (description "Switch")
      (fields (field (name "PUBLISHER") "Altium Limited"))
      (libsource (lib "Miscellaneous Devices") (part "SW-PB"))
    )
    (comp (ref "SW")
      (value "SW SPDT")
      (footprint "PW_SW")
      (description "SPDT Subminiature Toggle Switch, Right Angle Mounting, Vertical Actuation")
      (fields (field (name "PUBLISHER") "Altium Limited"))
      (libsource (lib "Miscellaneous Devices") (part "SW-SPDT"))
    )
    (comp (ref "U1")
      (value "LM1117S-2.5")
      (footprint "SOT-223")
      (description "Header, 4-Pin")
      (fields (field (name "PUBLISHER") "Altium Limited"))
      (libsource (lib "Miscellaneous Connectors") (part "Header 4"))
    )
    (comp (ref "U2")
      (value "LM1117T-3.3")
      (footprint "TO-252")
      (description "Header, 4-Pin")
      (fields (field (name "PUBLISHER") "Altium Limited"))
      (libsource (lib "Miscellaneous Connectors") (part "Header 4"))
    )
    (comp (ref "U3")
      (value "TF_CARD")
      (footprint "TF-2")
      (libsource (lib "ZJUNlict_design") (part "TF_CARD"))
    )
    (comp (ref "U4") (value "EP3C25") (footprint "PQFP240") (libsource (lib "EP3C25") (part "EP3C25Q240C8")))
    (comp (ref "U5")
      (value "MAX811T")
      (footprint "SOT143")
      (description "Header, 4-Pin")
      (fields (field (name "PUBLISHER") "Altium Limited"))
      (libsource (lib "Miscellaneous Connectors") (part "Header 4"))
    )
    (comp (ref "U7") (value "SW") (footprint "SW_PORT") (libsource (lib "ZJUNlict_design") (part "SW")))
    (comp (ref "U10")
      (value "EPCS4")
      (footprint "SO-G8")
      (description "Header, 8-Pin")
      (fields (field (name "PUBLISHER") "Altium Limited"))
      (libsource (lib "Miscellaneous Connectors") (part "Header 8"))
    )
    (comp (ref "U13")
      (value "STM32F407ZET6")
      (footprint "LQFP144")
      (libsource (lib "ZJUNlict_design") (part "STM32F407ZET6"))
    )
    (comp (ref "X1")
      (value "CLOCK_SOURCE")
      (footprint "CRYSTAL4")
      (description "Header, 4-Pin")
      (fields (field (name "PUBLISHER") "Altium Limited"))
      (libsource (lib "Miscellaneous Connectors") (part "Header 4"))
    )
    (comp (ref "X2")
      (value "CLOCK_SOURCE")
      (footprint "CRYSTAL4")
      (description "Header, 4-Pin")
      (fields (field (name "PUBLISHER") "Altium Limited"))
      (libsource (lib "Miscellaneous Connectors") (part "Header 4"))
    )
    (comp (ref "X4")
      (value "8MHZ")
      (footprint "5032")
      (description "Crystal Oscillator")
      (fields (field (name "PUBLISHER") "Altium Limited"))
      (libsource (lib "Miscellaneous Devices") (part "XTAL"))
    )
  )
  (nets
    (net (code "1") (name "/4") (class "Default")
      (node (ref "P10") (pin "47") (pinfunction "4_47") (pintype "bidirectional"))
      (node (ref "U4") (pin "4") (pinfunction "IO,_DIFFIO_L1p_4") (pintype "bidirectional"))
    )
    (net (code "2") (name "/5") (class "Default")
      (node (ref "P10") (pin "48") (pinfunction "5_48") (pintype "bidirectional"))
      (node (ref "U4") (pin "5") (pinfunction "IO,_DIFFIO_L1n_5") (pintype "bidirectional"))
    )
    (net (code "3") (name "/6") (class "Default")
      (node (ref "U4") (pin "6") (pinfunction "IO_6") (pintype "bidirectional"))
    )
    (net (code "4") (name "/9") (class "Default")
      (node (ref "D0") (pin "2") (pinfunction "K_2") (pintype "passive"))
      (node (ref "U4") (pin "9") (pinfunction "IO,_(DQS2L/CQ3L,CDPCLK0)_9") (pintype "bidirectional"))
    )
    (net (code "5") (name "/13") (class "Default")
      (node (ref "D1") (pin "2") (pinfunction "K_2") (pintype "passive"))
      (node (ref "U4") (pin "13") (pinfunction "IO,_VREFB1N0_13") (pintype "bidirectional"))
    )
    (net (code "6") (name "/18") (class "Default")
      (node (ref "D2") (pin "2") (pinfunction "K_2") (pintype "passive"))
      (node (ref "U4") (pin "18") (pinfunction "IO_18") (pintype "bidirectional"))
    )
    (net (code "7") (name "/21") (class "Default")
      (node (ref "D3") (pin "2") (pinfunction "K_2") (pintype "passive"))
      (node (ref "U4") (pin "21") (pinfunction "IO,_DIFFIO_L6p,_(DQS0L/CQ1L,DPCLK0)_21") (pintype "bidirectional"))
    )
    (net (code "8") (name "/22") (class "Default")
      (node (ref "U4") (pin "22") (pinfunction "IO,_DIFFIO_L6n_22") (pintype "bidirectional"))
    )
    (net (code "9") (name "/32_1") (class "Default")
      (node (ref "U13") (pin "1") (pinfunction "PE2/TRACECLK/FSMC_A23/ETH_MII_TXD3_1") (pintype "passive"))
    )
    (net (code "10") (name "/32_2") (class "Default")
      (node (ref "U13") (pin "2") (pinfunction "PE3/TRACED0/FSMC_A19_2") (pintype "passive"))
    )
    (net (code "11") (name "/32_3") (class "Default")
      (node (ref "U13") (pin "3") (pinfunction "PE4/TRACED1/FSMC_A20/DCMI_D4_3") (pintype "passive"))
    )
    (net (code "12") (name "/32_4") (class "Default")
      (node (ref "U13") (pin "4") (pinfunction "PE5/TRACED2/FSMC_A21/TIM9_CH1/DCMI_D6_4") (pintype "passive"))
    )
    (net (code "13") (name "/32_5") (class "Default")
      (node (ref "U13") (pin "5") (pinfunction "PE6/TRACED3/FSMC_A22/TIM9_CH2/DCMI_D7_5") (pintype "passive"))
    )
    (net (code "14") (name "/32_7") (class "Default")
      (node (ref "U13") (pin "7") (pinfunction "PC13/RTC_AF1_7") (pintype "passive"))
    )
    (net (code "15") (name "/32_9D_INT") (class "Default")
      (node (ref "U13") (pin "26") (pinfunction "PC0/OTG_HS_ULPI_STP/ADC123_IN10_26") (pintype "passive"))
    )
    (net (code "16") (name "/32_10") (class "Default")
      (node (ref "U13") (pin "10") (pinfunction "PF0/FSMC_A0/I2C2_SDA_10") (pintype "passive"))
    )
    (net (code "17") (name "/32_11") (class "Default")
      (node (ref "U13") (pin "11") (pinfunction "PF1/FSMC_A1/I2C2_SCL_11") (pintype "passive"))
    )
    (net (code "18") (name "/32_13") (class "Default")
      (node (ref "U13") (pin "13") (pinfunction "PF3/FSMC_A3/ADC3_IN9_13") (pintype "passive"))
    )
    (net (code "19") (name "/32_14") (class "Default")
      (node (ref "U13") (pin "14") (pinfunction "PF4/FSMC_A4/ADC3_IN14_14") (pintype "passive"))
    )
    (net (code "20") (name "/32_15") (class "Default")
      (node (ref "U13") (pin "15") (pinfunction "PF5/FSMC_A5/ADC3_IN15_15") (pintype "passive"))
    )
    (net (code "21") (name "/32_18") (class "Default")
      (node (ref "U13") (pin "18") (pinfunction "PF6/TIM10_CH1/FSMC_NIORD/ADC3_IN4_18") (pintype "passive"))
    )
    (net (code "22") (name "/32_19") (class "Default")
      (node (ref "U13") (pin "19") (pinfunction "PF7/TIM11_CH1/FSMC_NREG/ADC3_IN5_19") (pintype "passive"))
    )
    (net (code "23") (name "/32_20") (class "Default")
      (node (ref "U13") (pin "20") (pinfunction "PF8/TIM13_CH1/FSMC_NIOWR/ADC3_IN6_20") (pintype "passive"))
    )
    (net (code "24") (name "/32_21") (class "Default")
      (node (ref "D4") (pin "2") (pinfunction "K_2") (pintype "passive"))
      (node (ref "U13") (pin "21") (pinfunction "PF9/TIM14_CH1/FSMC_CD/ADC3_IN7_21") (pintype "passive"))
    )
    (net (code "25") (name "/32_22") (class "Default")
      (node (ref "D6") (pin "2") (pinfunction "K_2") (pintype "passive"))
      (node (ref "U13") (pin "22") (pinfunction "PF10/FSMC_INTR/ADC3_IN8_22") (pintype "passive"))
    )
    (net (code "26") (name "/32_27") (class "Default")
      (node (ref "U13") (pin "27") (pinfunction "PC1/ETH_MDC/ADC123_IN11_27") (pintype "passive"))
    )
    (net (code "27") (name "/32_28") (class "Default")
      (node (ref "U13") (pin "28") (pinfunction "PC2/SPI2_MISO/OTG_HS_ULPI_DIR/ETH_MII_TXD2/I2S2ext_SD/ADC123_IN12_28") (pintype "passive"))
    )
    (net (code "28") (name "/32_29") (class "Default")
      (node (ref "U13") (pin "29") (pinfunction "PC3/SPI2_MOSI/OTG_HS_ULPI_NXT/ETH_MII_TX_CLK/I2S2_SD/ADC123_IN13_29") (pintype "passive"))
    )
    (net (code "29") (name "/32_34") (class "Default")
      (node (ref "U13") (pin "34") (pinfunction "PA0-WKUP/U2_CTS/U4_TX/ETH_MII_CRS/TIM2_CH1_ETR/TIM5_CH1/TIM8_ETR/ADC123_IN0_34") (pintype "passive"))
    )
    (net (code "30") (name "/32_35") (class "Default")
      (node (ref "U13") (pin "35") (pinfunction "PA1/U2_RTS/U4_RX/ETH_RMII_REF_CLK/ETH_MII_RX_CLK/TIM2_CH2/TIM5_CH2/ADC123_IN1_35") (pintype "passive"))
    )
    (net (code "31") (name "/32_36") (class "Default")
      (node (ref "U13") (pin "36") (pinfunction "PA2/U2_TX/TIM2_CH3/TIM5_CH3/TIM9_CH1/ETH_MDIO/ADC123_IN2_36") (pintype "passive"))
    )
    (net (code "32") (name "/32_37") (class "Default")
      (node (ref "U13") (pin "37") (pinfunction "PA3/U2_RX/TIM2_CH4/TIM5_CH4/TIM9_CH2/OTG_HS_ULPI_D0/ETH_MII_COL/ADC123_IN3_37") (pintype "passive"))
    )
    (net (code "33") (name "/32_40") (class "Default")
      (node (ref "U13") (pin "40") (pinfunction "PA4/SPI1_NSS/U2_CK/DCMI_HSYNC/OTG_HS_SOF/I2S3_WS/DAC1_OUT/ADC12_IN4_40") (pintype "passive"))
    )
    (net (code "34") (name "/32_41") (class "Default")
      (node (ref "U13") (pin "41") (pinfunction "PA5/SPI1_SCK/OTG_HS_ULPI_CK/TIM2_CH1_ETR/TIM8_CH1N/DAC2_OUT/ADC12_IN5_41") (pintype "passive"))
    )
    (net (code "35") (name "/32_42") (class "Default")
      (node (ref "U13") (pin "42") (pinfunction "PA6/SPI1_MISO/TIM1_BKIN/TIM3_CH1/TIM8_BKIN/TIM13_CH1/DCMI_PIXCLK/ADC12_IN6_42") (pintype "passive"))
    )
    (net (code "36") (name "/32_43") (class "Default")
      (node (ref "U13") (pin "43") (pinfunction "PA7/SPI1_MOSI/TIM1_CH1N/TIM3_CH2/TIM8_CH1N/TIM14_CH1/ETH_MII_RX_DV/ETH_RMII_CRS_DV/ADC12_IN7_43") (pintype "passive"))
    )
    (net (code "37") (name "/32_44") (class "Default")
      (node (ref "U13") (pin "44") (pinfunction "PC4/ETH_MII_RXD0/ETH_RMII_RXD0/ADC12_IN14_44") (pintype "passive"))
    )
    (net (code "38") (name "/32_45") (class "Default")
      (node (ref "U13") (pin "45") (pinfunction "PC5/ETH_MII_RXD1/ETH_RMII_RXD1/ADC12_IN15_45") (pintype "passive"))
    )
    (net (code "39") (name "/32_46") (class "Default")
      (node (ref "U13") (pin "46") (pinfunction "PB0/TIM1_CH2N/TIM3_CH3/TIM8_CH2N/OTG_HS_ULPI_D1/ETH_MII_RXD2/ADC12_IN8_46") (pintype "passive"))
    )
    (net (code "40") (name "/32_47") (class "Default")
      (node (ref "U13") (pin "47") (pinfunction "PB1/TIM1_CH3N/TIM3_CH4/TIM8_CH3N/OTG_HS_INTN/ETH_MII_RXD3/ADC12_IN9_47") (pintype "passive"))
    )
    (net (code "41") (name "/32_49") (class "Default")
      (node (ref "U13") (pin "49") (pinfunction "PF11/DCMI_D12_49") (pintype "passive"))
    )
    (net (code "42") (name "/32_50") (class "Default")
      (node (ref "U13") (pin "50") (pinfunction "PF12/FSMC_A6_50") (pintype "passive"))
    )
    (net (code "43") (name "/32_53") (class "Default")
      (node (ref "U13") (pin "53") (pinfunction "PF13/FSMC_A7_53") (pintype "passive"))
    )
    (net (code "44") (name "/32_54") (class "Default")
      (node (ref "U13") (pin "54") (pinfunction "PF14/FSMC_A8_54") (pintype "passive"))
    )
    (net (code "45") (name "/32_55") (class "Default")
      (node (ref "U13") (pin "55") (pinfunction "PF15/FSMC_A9_55") (pintype "passive"))
    )
    (net (code "46") (name "/32_56") (class "Default")
      (node (ref "U13") (pin "56") (pinfunction "PG0/FSMC_A10_56") (pintype "passive"))
    )
    (net (code "47") (name "/32_57") (class "Default")
      (node (ref "U13") (pin "57") (pinfunction "PG1/FSMC_A11_57") (pintype "passive"))
    )
    (net (code "48") (name "/32_58") (class "Default")
      (node (ref "U13") (pin "58") (pinfunction "PE7/FSMC_D4/TIM1_ETR_58") (pintype "passive"))
    )
    (net (code "49") (name "/32_59") (class "Default")
      (node (ref "U13") (pin "59") (pinfunction "PE8/FSMC_D5/TIM1_CH1N_59") (pintype "passive"))
    )
    (net (code "50") (name "/32_60") (class "Default")
      (node (ref "U13") (pin "60") (pinfunction "PE9/FSMC_D6/TIM1_CH1_60") (pintype "passive"))
    )
    (net (code "51") (name "/32_63") (class "Default")
      (node (ref "U13") (pin "63") (pinfunction "PE10/FSMC_D7/TIM1_CH2N_63") (pintype "passive"))
    )
    (net (code "52") (name "/32_64") (class "Default")
      (node (ref "U13") (pin "64") (pinfunction "PE11/FSMC_D8/TIM1_CH2_64") (pintype "passive"))
    )
    (net (code "53") (name "/32_65") (class "Default")
      (node (ref "U13") (pin "65") (pinfunction "PE12/FSMC_D9/TIM1_CH3N_65") (pintype "passive"))
    )
    (net (code "54") (name "/32_66") (class "Default")
      (node (ref "U13") (pin "66") (pinfunction "PE13/FSMC_D10/TIM1_CH3_66") (pintype "passive"))
    )
    (net (code "55") (name "/32_67") (class "Default")
      (node (ref "U13") (pin "67") (pinfunction "PE14/FSMC_D11/TIM1_CH4_67") (pintype "passive"))
    )
    (net (code "56") (name "/32_68") (class "Default")
      (node (ref "U13") (pin "68") (pinfunction "PE15/FSMC_D12/TIM1_BKIN_68") (pintype "passive"))
    )
    (net (code "57") (name "/32_69") (class "Default")
      (node (ref "U13") (pin "69") (pinfunction "PB10/SPI2_SCK/TIM2_CH3/U3_TX/I2C2_SCL/OTG_HS_ULPI_D3/I2S2_CK_69") (pintype "passive"))
    )
    (net (code "58") (name "/32_70") (class "Default")
      (node (ref "U13") (pin "70") (pinfunction "PB11/TIM2_CH4/U3_RX/I2C2_SDA/HS_ULPI_D4/ETH_MII_TX_EN/ETH_RMII_TX_EN_70") (pintype "passive"))
    )
    (net (code "59") (name "/32_73") (class "Default")
      (node (ref "U13") (pin "73") (pinfunction "PB12/SPI2_NSS/TIM1_BKIN/U3_CK/CAN2_RX/I2C2_SMBA/OTG_HS_ULPI_D5/OTG_HS_ID/ETH_MII_TXD0/ETH_RMII_TXD0/I2S2_WS_73") (pintype "passive"))
    )
    (net (code "60") (name "/32_74") (class "Default")
      (node (ref "U13") (pin "74") (pinfunction "PB13/SPI2_SCK/TIM1_CH1N/U3_CTS/CAN2_TX/OTG_HS_ULPI_D6/OTG_HS_VBUS/ETH_MII_TXD1/ETH_RMII_TXD1/I2S2_CK_74") (pintype "passive"))
    )
    (net (code "61") (name "/32_75") (class "Default")
      (node (ref "U13") (pin "75") (pinfunction "PB14/SPI2_MISO/TIM1_CH2N/TIM8_CH2N/TIM12_CH1/U3_RTS/OTG_HS_DM/I2S2ext_SD_75") (pintype "passive"))
    )
    (net (code "62") (name "/32_76") (class "Default")
      (node (ref "U13") (pin "76") (pinfunction "PB15/SPI2_MOSI/TIM1_CH3N/TIM8_CH3N/TIM12_CH2/OTG_HS_DP/I2S2_SD_76") (pintype "passive"))
    )
    (net (code "63") (name "/32_77") (class "Default")
      (node (ref "U13") (pin "77") (pinfunction "PD8/FSMC_D13/U3_TX_77") (pintype "passive"))
    )
    (net (code "64") (name "/32_78") (class "Default")
      (node (ref "U13") (pin "78") (pinfunction "PD9/FSMC_D14/U3_RX_78") (pintype "passive"))
    )
    (net (code "65") (name "/32_79") (class "Default")
      (node (ref "U13") (pin "79") (pinfunction "PD10/FSMC_D15/U3_CK_79") (pintype "passive"))
    )
    (net (code "66") (name "/32_80") (class "Default")
      (node (ref "U13") (pin "80") (pinfunction "PD11/FSMC_A16/FSMC_CLE/U3_CTS_80") (pintype "passive"))
    )
    (net (code "67") (name "/32_81") (class "Default")
      (node (ref "U13") (pin "81") (pinfunction "PD12/FSMC_A17/FSMC_ALE/TIM4_CH1/U3_RTS_81") (pintype "passive"))
    )
    (net (code "68") (name "/32_82") (class "Default")
      (node (ref "U13") (pin "82") (pinfunction "PD13/FSMC_A18/TIM4_CH2_82") (pintype "passive"))
    )
    (net (code "69") (name "/32_85") (class "Default")
      (node (ref "U13") (pin "85") (pinfunction "PD14/FSMC_D0/TIM4_CH3_85") (pintype "passive"))
    )
    (net (code "70") (name "/32_86") (class "Default")
      (node (ref "U13") (pin "86") (pinfunction "PD15/FSMC_D1/TIM4_CH4_86") (pintype "passive"))
    )
    (net (code "71") (name "/32_87") (class "Default")
      (node (ref "U13") (pin "87") (pinfunction "PG2/FSMC_A12_87") (pintype "passive"))
    )
    (net (code "72") (name "/32_88") (class "Default")
      (node (ref "U13") (pin "88") (pinfunction "PG3/FSMC_A13_88") (pintype "passive"))
    )
    (net (code "73") (name "/32_89") (class "Default")
      (node (ref "U13") (pin "89") (pinfunction "PG4/FSMC_A14_89") (pintype "passive"))
    )
    (net (code "74") (name "/32_90") (class "Default")
      (node (ref "U13") (pin "90") (pinfunction "PG5/FSMC_A15_90") (pintype "passive"))
    )
    (net (code "75") (name "/32_91") (class "Default")
      (node (ref "U13") (pin "91") (pinfunction "PG6/FSMC_INT2_91") (pintype "passive"))
    )
    (net (code "76") (name "/32_92") (class "Default")
      (node (ref "U13") (pin "92") (pinfunction "PG7/FSMC_INT3/U6_CK_92") (pintype "passive"))
    )
    (net (code "77") (name "/32_93") (class "Default")
      (node (ref "U13") (pin "93") (pinfunction "PG8/U6_RTS/ETH_PPS_OUT_93") (pintype "passive"))
    )
    (net (code "78") (name "/32_96") (class "Default")
      (node (ref "U13") (pin "96") (pinfunction "PC6/TIM3_CH1/TIM8_CH1/U6_TX/SDIO_D6/DCMI_D0/I2S2_MCK_96") (pintype "passive"))
    )
    (net (code "79") (name "/32_97") (class "Default")
      (node (ref "U13") (pin "97") (pinfunction "PC7/TIM3_CH2/TIM8_CH2/U6_RX/SDIO_D7/DCMI_D1/I2S3_MCK_97") (pintype "passive"))
    )
    (net (code "80") (name "/32_100") (class "Default")
      (node (ref "U13") (pin "100") (pinfunction "PA8/TIM1_CH1/U1_CK/I2C3_SCL/MCO1/OTG_FS_SOF_100") (pintype "passive"))
    )
    (net (code "81") (name "/32_101") (class "Default")
      (node (ref "U13") (pin "101") (pinfunction "PA9/TIM1_CH2/U1_TX/I2C3_SMBA/OTG_FS_VBUS/DCMI_D0_101") (pintype "passive"))
    )
    (net (code "82") (name "/32_102") (class "Default")
      (node (ref "U13") (pin "102") (pinfunction "PA10/TIM1_CH3/U1_RX/OTG_FS_ID/DCMI_D1_102") (pintype "passive"))
    )
    (net (code "83") (name "/32_103") (class "Default")
      (node (ref "U13") (pin "103") (pinfunction "PA11/TIM1_CH4/U1_CTS/CAN1_RX/OTG_FS_DM_103") (pintype "passive"))
    )
    (net (code "84") (name "/32_104") (class "Default")
      (node (ref "U13") (pin "104") (pinfunction "PA12/TIM1_ETR/U1_RTS/CAN1_TX/OTG_FS_DP_104") (pintype "passive"))
    )
    (net (code "85") (name "/32_114") (class "Default")
      (node (ref "U13") (pin "114") (pinfunction "PD0/FSMC_D2/CAN1_RX_114") (pintype "passive"))
    )
    (net (code "86") (name "/32_115") (class "Default")
      (node (ref "U13") (pin "115") (pinfunction "PD1/FSMC_D3/CAN1_TX_115") (pintype "passive"))
    )
    (net (code "87") (name "/32_117") (class "Default")
      (node (ref "U13") (pin "117") (pinfunction "PD3/FSMC_CLK/U2_CTS_117") (pintype "passive"))
    )
    (net (code "88") (name "/32_118") (class "Default")
      (node (ref "U13") (pin "118") (pinfunction "PD4/FSMC_NOE/U2_RTS_118") (pintype "passive"))
    )
    (net (code "89") (name "/32_119") (class "Default")
      (node (ref "U13") (pin "119") (pinfunction "PD5/FSMC_NWE/U2_TX_119") (pintype "passive"))
    )
    (net (code "90") (name "/32_122") (class "Default")
      (node (ref "U13") (pin "122") (pinfunction "PD6/FSMC_NWAIT/U2_RX_122") (pintype "passive"))
    )
    (net (code "91") (name "/32_123") (class "Default")
      (node (ref "U13") (pin "123") (pinfunction "PD7/FSMC_NE1/FSMC_NCE2/U2_CK_123") (pintype "passive"))
    )
    (net (code "92") (name "/32_124") (class "Default")
      (node (ref "U13") (pin "124") (pinfunction "PG9/FSMC_NE2/FSMC_NCE3/U6_RX_124") (pintype "passive"))
    )
    (net (code "93") (name "/32_125") (class "Default")
      (node (ref "U13") (pin "125") (pinfunction "PG10/FSMC_NCE4_1/FSMC_NE3_125") (pintype "passive"))
    )
    (net (code "94") (name "/32_126") (class "Default")
      (node (ref "U13") (pin "126") (pinfunction "PG11/FSMC_NCE4_2/ETH_MII_TX_EN/ETH_RMII_TX_EN_126") (pintype "passive"))
    )
    (net (code "95") (name "/32_127") (class "Default")
      (node (ref "U13") (pin "127") (pinfunction "PG12/FSMC_NE4/U6_RTS_127") (pintype "passive"))
    )
    (net (code "96") (name "/32_128") (class "Default")
      (node (ref "U13") (pin "128") (pinfunction "PG13/FSMC_A24/U6_CTS/ETH_MII_TXD0/ETH_RMII_TXD0_128") (pintype "passive"))
    )
    (net (code "97") (name "/32_129") (class "Default")
      (node (ref "U13") (pin "129") (pinfunction "PG14/FSMC_A25/U6_TX/ETH_MII_TXD1/ETH_RMII_TXD1_129") (pintype "passive"))
    )
    (net (code "98") (name "/32_132") (class "Default")
      (node (ref "U13") (pin "132") (pinfunction "PG15/U6_CTS/DCMI_D13_132") (pintype "passive"))
    )
    (net (code "99") (name "/32_133") (class "Default")
      (node (ref "U13") (pin "133") (pinfunction "PB3/JTDO/TRACESWO/TIM2_CH2/SPI1_SCK/SPI3_SCK/I2S3_CK_133") (pintype "passive"))
    )
    (net (code "100") (name "/32_134") (class "Default")
      (node (ref "U13") (pin "134") (pinfunction "PB4/JNTRST/TIM3_CH1/SPI1_MISO/SPI3_MISO/I2S3ext_SD_134") (pintype "passive"))
    )
    (net (code "101") (name "/32_135") (class "Default")
      (node (ref "U13") (pin "135") (pinfunction "PB5/TIM3_CH2/SPI1_MOSI/SPI3_MOSI/CAN2_RX/I2C1_SMBA/OTG_HS_ULPI_D7/ETH_PPS_OUT/DCMI_D10/I2S3_SD_135") (pintype "passive"))
    )
    (net (code "102") (name "/32_136") (class "Default")
      (node (ref "U13") (pin "136") (pinfunction "PB6/TIM4_CH1/U1_TX/CAN2_TX/I2C1_SCL/DCMI_D5_136") (pintype "passive"))
    )
    (net (code "103") (name "/32_137") (class "Default")
      (node (ref "U13") (pin "137") (pinfunction "PB7/TIM4_CH2/U1_RX/FSMC_NL/I2C1_SDA/DCMI_VSYNC_137") (pintype "passive"))
    )
    (net (code "104") (name "/32_BOOT0") (class "Default")
      (node (ref "R39") (pin "1") (pinfunction "1_1") (pintype "passive"))
      (node (ref "U13") (pin "138") (pinfunction "BOOT0_138") (pintype "passive"))
    )
    (net (code "105") (name "/32_BOOT1") (class "Default")
      (node (ref "R32") (pin "1") (pinfunction "1_1") (pintype "passive"))
      (node (ref "U13") (pin "48") (pinfunction "PB2/BOOT1_48") (pintype "passive"))
    )
    (net (code "106") (name "/32_FSMC_A2") (class "Default")
      (node (ref "U13") (pin "12") (pinfunction "PF2/FSMC_A2/I2C2_SMBA_12") (pintype "passive"))
    )
    (net (code "107") (name "/32_FSMC_NBL0") (class "Default")
      (node (ref "U13") (pin "141") (pinfunction "PE0/TIM4_ETR/FSMC_NBL0/DCMI_D2_141") (pintype "passive+no_connect"))
    )
    (net (code "108") (name "/32_FSMC_NBL1") (class "Default")
      (node (ref "U13") (pin "142") (pinfunction "PE1/FSMC_NBL1/DCMI_D3_142") (pintype "passive+no_connect"))
    )
    (net (code "109") (name "/32_IIC_SCL") (class "Default")
      (node (ref "P2") (pin "3") (pinfunction "3_3") (pintype "passive"))
      (node (ref "U13") (pin "139") (pinfunction "PB8/TIM4_CH3/TIM10_CH1/CAN1_RX/SDIO_D4/ETH_MII_TXD3/I2C1_SCL/DCMI_D6_139") (pintype "passive"))
    )
    (net (code "110") (name "/32_IIC_SDA") (class "Default")
      (node (ref "P2") (pin "4") (pinfunction "4_4") (pintype "passive"))
      (node (ref "U13") (pin "140") (pinfunction "PB9/TIM4_CH4/TIM11_CH1/CAN1_TX/SDIO_D5/SPI2_NSS/I2C1_SDA/DCMI_D7/I2S2_WS_140") (pintype "passive"))
    )
    (net (code "111") (name "/32_JTDI") (class "Default")
      (node (ref "U13") (pin "110") (pinfunction "PA15/JTDI/SPI1_NSS/SPI3_NSS/TIM2_CH1_ETR/I2S3_WS_110") (pintype "passive"))
    )
    (net (code "112") (name "/32_RESET") (class "Default")
      (node (ref "32_RESET") (pin "1") (pinfunction "1_1") (pintype "passive"))
      (node (ref "C77") (pin "2") (pinfunction "2_2") (pintype "passive"))
      (node (ref "R33") (pin "1") (pinfunction "1_1") (pintype "passive"))
      (node (ref "U13") (pin "25") (pinfunction "NRST_25") (pintype "passive"))
    )
    (net (code "113") (name "/32_SDIO_CMD") (class "Default")
      (node (ref "R48") (pin "2") (pinfunction "2_2") (pintype "passive"))
      (node (ref "U13") (pin "116") (pinfunction "PD2/TIM3_ETR/U5_RX/SDIO_CMD/DCMI_D11_116") (pintype "passive"))
      (node (ref "U3") (pin "3") (pinfunction "CMD_3") (pintype "passive"))
    )
    (net (code "114") (name "/32_SDIO_D0") (class "Default")
      (node (ref "R44") (pin "2") (pinfunction "2_2") (pintype "passive"))
      (node (ref "U13") (pin "98") (pinfunction "PC8/TIM3_CH3/TIM8_CH3/U6_CK/SDIO_D0/DCMI_D2_98") (pintype "passive"))
      (node (ref "U3") (pin "7") (pinfunction "DATA0_7") (pintype "passive"))
    )
    (net (code "115") (name "/32_SDIO_D1") (class "Default")
      (node (ref "R43") (pin "2") (pinfunction "2_2") (pintype "passive"))
      (node (ref "U13") (pin "99") (pinfunction "PC9/TIM3_CH4/TIM8_CH4/I2C3_SDA/SDIO_D1/DCMI_D3/MCO2/I2S_CKIN_99") (pintype "passive"))
      (node (ref "U3") (pin "8") (pinfunction "DATA1_8") (pintype "passive"))
    )
    (net (code "116") (name "/32_SDIO_D2") (class "Default")
      (node (ref "R46") (pin "2") (pinfunction "2_2") (pintype "passive"))
      (node (ref "U13") (pin "111") (pinfunction "PC10/SPI3_SCK/U3_TX/U4_TX/SDIO_D2/DCMI_D8/I2S3_CK_111") (pintype "passive"))
      (node (ref "U3") (pin "1") (pinfunction "DATA2_1") (pintype "passive"))
    )
    (net (code "117") (name "/32_SDIO_D3") (class "Default")
      (node (ref "R45") (pin "2") (pinfunction "2_2") (pintype "passive"))
      (node (ref "U13") (pin "112") (pinfunction "PC11/SPI3_MISO/U3_RX/U4_RX/SDIO_D3/DCMI_D4/I2S3ext_SD_112") (pintype "passive"))
      (node (ref "U3") (pin "2") (pinfunction "CD/DATA3_2") (pintype "passive"))
    )
    (net (code "118") (name "/32_SDIO_SCK") (class "Default")
      (node (ref "U13") (pin "113") (pinfunction "PC12/SPI3_MOSI/U3_CK/U5_TX/SDIO_CK/DCMI_D9/I2S3_SD_113") (pintype "passive"))
      (node (ref "U3") (pin "5") (pinfunction "CLK_5") (pintype "passive"))
    )
    (net (code "119") (name "/32_SWCLK") (class "Default")
      (node (ref "R36") (pin "1") (pinfunction "1_1") (pintype "passive"))
      (node (ref "U13") (pin "109") (pinfunction "PA14/JTCK_SWCLK_109") (pintype "passive"))
      (node (ref "U7") (pin "2") (pinfunction "SWCLK_2") (pintype "passive"))
    )
    (net (code "120") (name "/32_SWDIO") (class "Default")
      (node (ref "R38") (pin "2") (pinfunction "2_2") (pintype "passive"))
      (node (ref "U13") (pin "105") (pinfunction "PA13/JTMS_SWDIO_105") (pintype "passive"))
      (node (ref "U7") (pin "4") (pinfunction "SWDIO_4") (pintype "passive"))
    )
    (net (code "121") (name "/32_VCC_3.3") (class "Default")
      (node (ref "C11") (pin "2") (pinfunction "2_2") (pintype "passive"))
      (node (ref "C13") (pin "2") (pinfunction "2_2") (pintype "passive"))
      (node (ref "C16") (pin "2") (pinfunction "2_2") (pintype "passive"))
      (node (ref "C19") (pin "2") (pinfunction "2_2") (pintype "passive"))
      (node (ref "C2") (pin "2") (pinfunction "2_2") (pintype "passive"))
      (node (ref "C20") (pin "2") (pinfunction "2_2") (pintype "passive"))
      (node (ref "C21") (pin "2") (pinfunction "2_2") (pintype "passive"))
      (node (ref "C22") (pin "2") (pinfunction "2_2") (pintype "passive"))
      (node (ref "C31") (pin "2") (pinfunction "2_2") (pintype "passive"))
      (node (ref "C32") (pin "2") (pinfunction "2_2") (pintype "passive"))
      (node (ref "C35") (pin "2") (pinfunction "2_2") (pintype "passive"))
      (node (ref "C36") (pin "2") (pinfunction "2_2") (pintype "passive"))
      (node (ref "C45") (pin "2") (pinfunction "2_2") (pintype "passive"))
      (node (ref "C46") (pin "2") (pinfunction "2_2") (pintype "passive"))
      (node (ref "C47") (pin "2") (pinfunction "2_2") (pintype "passive"))
      (node (ref "C49") (pin "2") (pinfunction "2_2") (pintype "passive"))
      (node (ref "C5") (pin "2") (pinfunction "2_2") (pintype "passive"))
      (node (ref "C52") (pin "2") (pinfunction "2_2") (pintype "passive"))
      (node (ref "C54") (pin "2") (pinfunction "2_2") (pintype "passive"))
      (node (ref "C56") (pin "2") (pinfunction "2_2") (pintype "passive"))
      (node (ref "C57") (pin "2") (pinfunction "2_2") (pintype "passive"))
      (node (ref "C6") (pin "2") (pinfunction "2_2") (pintype "passive"))
      (node (ref "C64") (pin "2") (pinfunction "2_2") (pintype "passive"))
      (node (ref "C65") (pin "2") (pinfunction "2_2") (pintype "passive"))
      (node (ref "C66") (pin "2") (pinfunction "2_2") (pintype "passive"))
      (node (ref "C67") (pin "2") (pinfunction "2_2") (pintype "passive"))
      (node (ref "C73") (pin "2") (pinfunction "2_2") (pintype "passive"))
      (node (ref "C74") (pin "1") (pinfunction "1_1") (pintype "passive"))
      (node (ref "C80") (pin "2") (pinfunction "2_2") (pintype "passive"))
      (node (ref "C9") (pin "2") (pinfunction "2_2") (pintype "passive"))
      (node (ref "EPCS") (pin "4") (pinfunction "4_4") (pintype "passive"))
      (node (ref "JTAG") (pin "4") (pinfunction "4_4") (pintype "passive"))
      (node (ref "L4") (pin "2") (pinfunction "2_2") (pintype "passive"))
      (node (ref "L7") (pin "2") (pinfunction "2_2") (pintype "passive"))
      (node (ref "P10") (pin "148") (pinfunction "VCC_3.3_148") (pintype "power_in"))
      (node (ref "P10") (pin "52") (pinfunction "VCC_3.3_52") (pintype "power_in"))
      (node (ref "P2") (pin "1") (pinfunction "1_1") (pintype "passive"))
      (node (ref "R10") (pin "1") (pinfunction "1_1") (pintype "passive"))
      (node (ref "R11") (pin "2") (pinfunction "2_2") (pintype "passive"))
      (node (ref "R12") (pin "2") (pinfunction "2_2") (pintype "passive"))
      (node (ref "R13") (pin "2") (pinfunction "2_2") (pintype "passive"))
      (node (ref "R16") (pin "2") (pinfunction "2_2") (pintype "passive"))
      (node (ref "R17") (pin "2") (pinfunction "2_2") (pintype "passive"))
      (node (ref "R18") (pin "2") (pinfunction "2_2") (pintype "passive"))
      (node (ref "R22") (pin "1") (pinfunction "1_1") (pintype "passive"))
      (node (ref "R25") (pin "2") (pinfunction "2_2") (pintype "passive"))
      (node (ref "R3") (pin "1") (pinfunction "1_1") (pintype "passive"))
      (node (ref "R33") (pin "2") (pinfunction "2_2") (pintype "passive"))
      (node (ref "R36") (pin "2") (pinfunction "2_2") (pintype "passive"))
      (node (ref "R4") (pin "1") (pinfunction "1_1") (pintype "passive"))
      (node (ref "R40") (pin "2") (pinfunction "2_2") (pintype "passive"))
      (node (ref "R41") (pin "2") (pinfunction "2_2") (pintype "passive"))
      (node (ref "R42") (pin "2") (pinfunction "2_2") (pintype "passive"))
      (node (ref "R43") (pin "1") (pinfunction "1_1") (pintype "passive"))
      (node (ref "R44") (pin "1") (pinfunction "1_1") (pintype "passive"))
      (node (ref "R45") (pin "1") (pinfunction "1_1") (pintype "passive"))
      (node (ref "R46") (pin "1") (pinfunction "1_1") (pintype "passive"))
      (node (ref "R48") (pin "1") (pinfunction "1_1") (pintype "passive"))
      (node (ref "R7") (pin "1") (pinfunction "1_1") (pintype "passive"))
      (node (ref "R9") (pin "1") (pinfunction "1_1") (pintype "passive"))
      (node (ref "U10") (pin "3") (pinfunction "3_3") (pintype "passive"))
      (node (ref "U10") (pin "7") (pinfunction "7_7") (pintype "passive"))
      (node (ref "U10") (pin "8") (pinfunction "8_8") (pintype "passive"))
      (node (ref "U13") (pin "108") (pinfunction "VDD_108") (pintype "passive"))
      (node (ref "U13") (pin "121") (pinfunction "VDD_121") (pintype "passive"))
      (node (ref "U13") (pin "131") (pinfunction "VDD_131") (pintype "passive"))
      (node (ref "U13") (pin "143") (pinfunction "PDR_ON_143") (pintype "passive"))
      (node (ref "U13") (pin "144") (pinfunction "VDD_144") (pintype "passive"))
      (node (ref "U13") (pin "17") (pinfunction "VDD_17") (pintype "passive"))
      (node (ref "U13") (pin "30") (pinfunction "VDD_30") (pintype "passive"))
      (node (ref "U13") (pin "32") (pinfunction "Vref+_32") (pintype "passive"))
      (node (ref "U13") (pin "39") (pinfunction "VDD_39") (pintype "passive"))
      (node (ref "U13") (pin "52") (pinfunction "VDD_52") (pintype "passive"))
      (node (ref "U13") (pin "6") (pinfunction "VBAT_6") (pintype "passive"))
      (node (ref "U13") (pin "62") (pinfunction "VDD_62") (pintype "passive"))
      (node (ref "U13") (pin "72") (pinfunction "VDD_72") (pintype "passive"))
      (node (ref "U13") (pin "84") (pinfunction "VDD_84") (pintype "passive"))
      (node (ref "U13") (pin "95") (pinfunction "VDD_95") (pintype "passive"))
      (node (ref "U2") (pin "2") (pinfunction "2_2") (pintype "passive"))
      (node (ref "U3") (pin "4") (pinfunction "VDD_4") (pintype "passive"))
      (node (ref "U4") (pin "104") (pinfunction "VCCIO4_104") (pintype "power_in"))
      (node (ref "U4") (pin "124") (pinfunction "VCCIO5_124") (pintype "power_in"))
      (node (ref "U4") (pin "136") (pinfunction "VCCIO5_136") (pintype "power_in"))
      (node (ref "U4") (pin "15") (pinfunction "VCCIO1_15") (pintype "power_in"))
      (node (ref "U4") (pin "154") (pinfunction "VCCIO6_154") (pintype "power_in"))
      (node (ref "U4") (pin "170") (pinfunction "VCCIO6_170") (pintype "power_in"))
      (node (ref "U4") (pin "192") (pinfunction "VCCIO7_192") (pintype "power_in"))
      (node (ref "U4") (pin "206") (pinfunction "VCCIO7_206") (pintype "power_in"))
      (node (ref "U4") (pin "213") (pinfunction "VCCIO8_213") (pintype "power_in"))
      (node (ref "U4") (pin "225") (pinfunction "VCCIO8_225") (pintype "power_in"))
      (node (ref "U4") (pin "35") (pinfunction "VCCIO2_35") (pintype "power_in"))
      (node (ref "U4") (pin "47") (pinfunction "VCCIO2_47") (pintype "power_in"))
      (node (ref "U4") (pin "66") (pinfunction "VCCIO3_66") (pintype "power_in"))
      (node (ref "U4") (pin "7") (pinfunction "VCCIO1_7") (pintype "power_in"))
      (node (ref "U4") (pin "77") (pinfunction "VCCIO3_77") (pintype "power_in"))
      (node (ref "U4") (pin "96") (pinfunction "VCCIO4_96") (pintype "power_in"))
      (node (ref "U5") (pin "4") (pinfunction "4_4") (pintype "passive"))
      (node (ref "U7") (pin "8") (pinfunction "3.3V_8") (pintype "passive"))
    )
    (net (code "122") (name "/49") (class "Default")
      (node (ref "U4") (pin "49") (pinfunction "IO,_DIFFIO_L13p,_(DQ1L)_49") (pintype "bidirectional"))
    )
    (net (code "123") (name "/50") (class "Default")
      (node (ref "U4") (pin "50") (pinfunction "IO,_DIFFIO_L13n_50") (pintype "bidirectional"))
    )
    (net (code "124") (name "/51") (class "Default")
      (node (ref "U4") (pin "51") (pinfunction "IO,_RUP1,_(DQ1L)_51") (pintype "bidirectional"))
    )
    (net (code "125") (name "/52") (class "Default")
      (node (ref "U4") (pin "52") (pinfunction "IO,_RDN1,_(DQ1L)_52") (pintype "bidirectional"))
    )
    (net (code "126") (name "/55") (class "Default")
      (node (ref "U4") (pin "55") (pinfunction "IO,_(DQS3L/CQ3L#,CDPCLK1)_55") (pintype "bidirectional"))
    )
    (net (code "127") (name "/63") (class "Default")
      (node (ref "U4") (pin "63") (pinfunction "IO,_DIFFIO_B2p_63") (pintype "bidirectional"))
    )
    (net (code "128") (name "/64") (class "Default")
      (node (ref "U4") (pin "64") (pinfunction "IO,_DIFFIO_B2n_64") (pintype "bidirectional"))
    )
    (net (code "129") (name "/65") (class "Default")
      (node (ref "U4") (pin "65") (pinfunction "IO_65") (pintype "bidirectional"))
    )
    (net (code "130") (name "/68") (class "Default")
      (node (ref "U4") (pin "68") (pinfunction "IO,_(DQS1B/CQ1B#,CDPCLK2)_68") (pintype "bidirectional"))
    )
    (net (code "131") (name "/69") (class "Default")
      (node (ref "U4") (pin "69") (pinfunction "IO,_PLL1_CLKOUTp_69") (pintype "bidirectional"))
    )
    (net (code "132") (name "/70") (class "Default")
      (node (ref "U4") (pin "70") (pinfunction "IO,_PLL1_CLKOUTn_70") (pintype "bidirectional"))
    )
    (net (code "133") (name "/71") (class "Default")
      (node (ref "U4") (pin "71") (pinfunction "IO,_DIFFIO_B4p_71") (pintype "bidirectional"))
    )
    (net (code "134") (name "/72") (class "Default")
      (node (ref "U4") (pin "72") (pinfunction "IO,_DIFFIO_B4n_72") (pintype "bidirectional"))
    )
    (net (code "135") (name "/76") (class "Default")
      (node (ref "U4") (pin "76") (pinfunction "IO,_VREFB3N0_76") (pintype "bidirectional"))
    )
    (net (code "136") (name "/87") (class "Default")
      (node (ref "U4") (pin "87") (pinfunction "IO,_(DQ5B)_87") (pintype "bidirectional"))
    )
    (net (code "137") (name "/88") (class "Default")
      (node (ref "U4") (pin "88") (pinfunction "IO,_(DQ5B)_88") (pintype "bidirectional"))
    )
    (net (code "138") (name "/100") (class "Default")
      (node (ref "P10") (pin "81") (pinfunction "100_81") (pintype "bidirectional"))
      (node (ref "U4") (pin "100") (pinfunction "IO,_(DQ5B)_100") (pintype "bidirectional"))
    )
    (net (code "139") (name "/103") (class "Default")
      (node (ref "P10") (pin "83") (pinfunction "103_83") (pintype "bidirectional"))
      (node (ref "U4") (pin "103") (pinfunction "IO,_(DQ5B)_103") (pintype "bidirectional"))
    )
    (net (code "140") (name "/106") (class "Default")
      (node (ref "U4") (pin "106") (pinfunction "IO,_(DQS2B/CQ3B,DPCLK5)_106") (pintype "bidirectional"))
    )
    (net (code "141") (name "/107") (class "Default")
      (node (ref "P10") (pin "85") (pinfunction "107_85") (pintype "bidirectional"))
      (node (ref "U4") (pin "107") (pinfunction "IO,_VREFB4N0_107") (pintype "bidirectional"))
    )
    (net (code "142") (name "/108") (class "Default")
      (node (ref "U4") (pin "108") (pinfunction "IO,_DIFFIO_B20p_108") (pintype "bidirectional"))
    )
    (net (code "143") (name "/109") (class "Default")
      (node (ref "U4") (pin "109") (pinfunction "IO,_DIFFIO_B20n_109") (pintype "bidirectional"))
    )
    (net (code "144") (name "/110") (class "Default")
      (node (ref "P10") (pin "88") (pinfunction "110_88") (pintype "bidirectional"))
      (node (ref "U4") (pin "110") (pinfunction "IO_110") (pintype "bidirectional"))
    )
    (net (code "145") (name "/111") (class "Default")
      (node (ref "P10") (pin "89") (pinfunction "111_89") (pintype "bidirectional"))
      (node (ref "U4") (pin "111") (pinfunction "IO,_RUP2_111") (pintype "bidirectional"))
    )
    (net (code "146") (name "/112") (class "Default")
      (node (ref "P10") (pin "90") (pinfunction "112_90") (pintype "bidirectional"))
      (node (ref "U4") (pin "112") (pinfunction "IO,_RDN2_112") (pintype "bidirectional"))
    )
    (net (code "147") (name "/113") (class "Default")
      (node (ref "U4") (pin "113") (pinfunction "IO,_(DQS0B/CQ1B,CDPCLK3)_113") (pintype "bidirectional"))
    )
    (net (code "148") (name "/114") (class "Default")
      (node (ref "P10") (pin "92") (pinfunction "114_92") (pintype "bidirectional"))
      (node (ref "U4") (pin "114") (pinfunction "IO_114") (pintype "bidirectional"))
    )
    (net (code "149") (name "/117") (class "Default")
      (node (ref "U4") (pin "117") (pinfunction "IO,_PLL4_CLKOUTp_117") (pintype "bidirectional"))
    )
    (net (code "150") (name "/118") (class "Default")
      (node (ref "U4") (pin "118") (pinfunction "IO,_PLL4_CLKOUTn_118") (pintype "bidirectional"))
    )
    (net (code "151") (name "/119") (class "Default")
      (node (ref "P10") (pin "95") (pinfunction "119_95") (pintype "bidirectional"))
      (node (ref "U4") (pin "119") (pinfunction "IO,_DIFFIO_B25p_119") (pintype "bidirectional"))
    )
    (net (code "152") (name "/120") (class "Default")
      (node (ref "P10") (pin "96") (pinfunction "120_96") (pintype "bidirectional"))
      (node (ref "U4") (pin "120") (pinfunction "IO,_DIFFIO_B25n_120") (pintype "bidirectional"))
    )
    (net (code "153") (name "/126") (class "Default")
      (node (ref "P10") (pin "114") (pinfunction "126_114") (pintype "bidirectional"))
      (node (ref "U4") (pin "126") (pinfunction "IO,_RUP3,_(DQ1R)_126") (pintype "bidirectional"))
    )
    (net (code "154") (name "/127") (class "Default")
      (node (ref "P10") (pin "115") (pinfunction "127_115") (pintype "bidirectional"))
      (node (ref "U4") (pin "127") (pinfunction "IO,_RDN3,_(DQ1R)_127") (pintype "bidirectional"))
    )
    (net (code "155") (name "/128") (class "Default")
      (node (ref "P10") (pin "116") (pinfunction "128_116") (pintype "bidirectional"))
      (node (ref "U4") (pin "128") (pinfunction "IO,_(DQS3R/CQ3R#,CDPCLK4)_128") (pintype "bidirectional"))
    )
    (net (code "156") (name "/131") (class "Default")
      (node (ref "P10") (pin "117") (pinfunction "131_117") (pintype "bidirectional"))
      (node (ref "U4") (pin "131") (pinfunction "IO,_DIFFIO_R13n,_(DQ1R)_131") (pintype "bidirectional"))
    )
    (net (code "157") (name "/132") (class "Default")
      (node (ref "P10") (pin "118") (pinfunction "132_118") (pintype "bidirectional"))
      (node (ref "U4") (pin "132") (pinfunction "IO,_DIFFIO_R13p,_(DQ1R)_132") (pintype "bidirectional"))
    )
    (net (code "158") (name "/133") (class "Default")
      (node (ref "P10") (pin "119") (pinfunction "133_119") (pintype "bidirectional"))
      (node (ref "U4") (pin "133") (pinfunction "IO,_VREFB5N0_133") (pintype "bidirectional"))
    )
    (net (code "159") (name "/134") (class "Default")
      (node (ref "P10") (pin "120") (pinfunction "134_120") (pintype "bidirectional"))
      (node (ref "U4") (pin "134") (pinfunction "IO,_DIFFIO_R12n,_(DQ1R)_134") (pintype "bidirectional"))
    )
    (net (code "160") (name "/135") (class "Default")
      (node (ref "P10") (pin "121") (pinfunction "135_121") (pintype "bidirectional"))
      (node (ref "U4") (pin "135") (pinfunction "IO,_DIFFIO_R12p,_(DQ1R)_135") (pintype "bidirectional"))
    )
    (net (code "161") (name "/137") (class "Default")
      (node (ref "P10") (pin "126") (pinfunction "137_126") (pintype "bidirectional"))
      (node (ref "U4") (pin "137") (pinfunction "IO,_DIFFIO_R11n,_(DQ1R)_137") (pintype "bidirectional"))
    )
    (net (code "162") (name "/139") (class "Default")
      (node (ref "P10") (pin "127") (pinfunction "139_127") (pintype "bidirectional"))
      (node (ref "U4") (pin "139") (pinfunction "IO,_DIFFIO_R11p_139") (pintype "bidirectional"))
    )
    (net (code "163") (name "/142") (class "Default")
      (node (ref "P10") (pin "128") (pinfunction "142_128") (pintype "bidirectional"))
      (node (ref "U4") (pin "142") (pinfunction "IO,_DIFFIO_R10n_142") (pintype "bidirectional"))
    )
    (net (code "164") (name "/143") (class "Default")
      (node (ref "P10") (pin "129") (pinfunction "143_129") (pintype "bidirectional"))
      (node (ref "U4") (pin "143") (pinfunction "IO,_DIFFIO_R10p,_(DQS1R/CQ1R#,DPCLK6)_143") (pintype "bidirectional"))
    )
    (net (code "165") (name "/144") (class "Default")
      (node (ref "P10") (pin "130") (pinfunction "144_130") (pintype "bidirectional"))
      (node (ref "U4") (pin "144") (pinfunction "IO,_DIFFIO_R9n,_(DEV_OE)_144") (pintype "bidirectional"))
    )
    (net (code "166") (name "/145") (class "Default")
      (node (ref "P10") (pin "131") (pinfunction "145_131") (pintype "bidirectional"))
      (node (ref "U4") (pin "145") (pinfunction "IO,_DIFFIO_R9p,_(DEV_CLRn)_145") (pintype "bidirectional"))
    )
    (net (code "167") (name "/146") (class "Default")
      (node (ref "P10") (pin "132") (pinfunction "146_132") (pintype "bidirectional"))
      (node (ref "U4") (pin "146") (pinfunction "IO_146") (pintype "bidirectional"))
    )
    (net (code "168") (name "/147") (class "Default")
      (node (ref "P10") (pin "133") (pinfunction "147_133") (pintype "bidirectional"))
      (node (ref "U4") (pin "147") (pinfunction "IO,_DIFFIO_R7n_147") (pintype "bidirectional"))
    )
    (net (code "169") (name "/148") (class "Default")
      (node (ref "P10") (pin "134") (pinfunction "148_134") (pintype "bidirectional"))
      (node (ref "U4") (pin "148") (pinfunction "IO,_DIFFIO_R7p_148") (pintype "bidirectional"))
    )
    (net (code "170") (name "/159") (class "Default")
      (node (ref "P10") (pin "135") (pinfunction "159_135") (pintype "bidirectional"))
      (node (ref "U4") (pin "159") (pinfunction "IO,_DIFFIO_R5n,_(INIT_DONE)_159") (pintype "bidirectional"))
    )
    (net (code "171") (name "/160") (class "Default")
      (node (ref "P10") (pin "136") (pinfunction "160_136") (pintype "bidirectional"))
      (node (ref "U4") (pin "160") (pinfunction "IO,_DIFFIO_R5p,_(CRC_ERROR)_160") (pintype "bidirectional"))
    )
    (net (code "172") (name "/161") (class "Default")
      (node (ref "P10") (pin "137") (pinfunction "161_137") (pintype "bidirectional"))
      (node (ref "U4") (pin "161") (pinfunction "IO_161") (pintype "bidirectional"))
    )
    (net (code "173") (name "/162") (class "Default")
      (node (ref "P10") (pin "138") (pinfunction "162_138") (pintype "bidirectional"))
      (node (ref "U4") (pin "162") (pinfunction "IO,_DIFFIO_R4n,_(nCEO)_162") (pintype "bidirectional"))
    )
    (net (code "174") (name "/164") (class "Default")
      (node (ref "P10") (pin "139") (pinfunction "164_139") (pintype "bidirectional"))
      (node (ref "U4") (pin "164") (pinfunction "IO,_DIFFIO_R4p,_(CLKUSR)_164") (pintype "bidirectional"))
    )
    (net (code "175") (name "/166") (class "Default")
      (node (ref "P10") (pin "140") (pinfunction "166_140") (pintype "bidirectional"))
      (node (ref "U4") (pin "166") (pinfunction "IO,_(DQS0R/CQ1R,DPCLK7)_166") (pintype "bidirectional"))
    )
    (net (code "176") (name "/167") (class "Default")
      (node (ref "P10") (pin "141") (pinfunction "167_141") (pintype "bidirectional"))
      (node (ref "U4") (pin "167") (pinfunction "IO,_DIFFIO_R3n,_(nWE)_167") (pintype "bidirectional"))
    )
    (net (code "177") (name "/168") (class "Default")
      (node (ref "P10") (pin "142") (pinfunction "168_142") (pintype "bidirectional"))
      (node (ref "U4") (pin "168") (pinfunction "IO,_DIFFIO_R3p,_(nOE)_168") (pintype "bidirectional"))
    )
    (net (code "178") (name "/169") (class "Default")
      (node (ref "P10") (pin "143") (pinfunction "169_143") (pintype "bidirectional"))
      (node (ref "U4") (pin "169") (pinfunction "IO,_VREFB6N0_169") (pintype "bidirectional"))
    )
    (net (code "179") (name "/171") (class "Default")
      (node (ref "P10") (pin "144") (pinfunction "171_144") (pintype "bidirectional"))
      (node (ref "U4") (pin "171") (pinfunction "IO,_(RDY),_(DQ1R)_171") (pintype "bidirectional"))
    )
    (net (code "180") (name "/173") (class "Default")
      (node (ref "P10") (pin "145") (pinfunction "173_145") (pintype "bidirectional"))
      (node (ref "U4") (pin "173") (pinfunction "IO,_(PADD23)_173") (pintype "bidirectional"))
    )
    (net (code "181") (name "/176") (class "Default")
      (node (ref "P10") (pin "146") (pinfunction "176_146") (pintype "bidirectional"))
      (node (ref "U4") (pin "176") (pinfunction "IO,_DIFFIO_R1n,_(PADD20),_(DQS2R/CQ3R,CDPCLK5)_176") (pintype "bidirectional"))
    )
    (net (code "182") (name "/177") (class "Default")
      (node (ref "P10") (pin "147") (pinfunction "177_147") (pintype "bidirectional"))
      (node (ref "U4") (pin "177") (pinfunction "IO,_DIFFIO_R1p_177") (pintype "bidirectional"))
    )
    (net (code "183") (name "/181") (class "Default")
      (node (ref "P10") (pin "2") (pinfunction "181_2") (pintype "bidirectional"))
      (node (ref "U4") (pin "181") (pinfunction "IO_181") (pintype "bidirectional"))
    )
    (net (code "184") (name "/182") (class "Default")
      (node (ref "P10") (pin "3") (pinfunction "182_3") (pintype "bidirectional"))
      (node (ref "U4") (pin "182") (pinfunction "IO,_DIFFIO_T23n_182") (pintype "bidirectional"))
    )
    (net (code "185") (name "/183") (class "Default")
      (node (ref "P10") (pin "4") (pinfunction "183_4") (pintype "bidirectional"))
      (node (ref "U4") (pin "183") (pinfunction "IO,_DIFFIO_T23p,_(DQS0T/CQ1T,CDPCLK6)_183") (pintype "bidirectional"))
    )
    (net (code "186") (name "/184") (class "Default")
      (node (ref "P10") (pin "5") (pinfunction "184_5") (pintype "bidirectional"))
      (node (ref "U4") (pin "184") (pinfunction "IO_184") (pintype "bidirectional"))
    )
    (net (code "187") (name "/185") (class "Default")
      (node (ref "P10") (pin "6") (pinfunction "185_6") (pintype "bidirectional"))
      (node (ref "U4") (pin "185") (pinfunction "IO,_PLL2_CLKOUTn_185") (pintype "bidirectional"))
    )
    (net (code "188") (name "/186") (class "Default")
      (node (ref "P10") (pin "7") (pinfunction "186_7") (pintype "bidirectional"))
      (node (ref "U4") (pin "186") (pinfunction "IO,_PLL2_CLKOUTp_186") (pintype "bidirectional"))
    )
    (net (code "189") (name "/187") (class "Default")
      (node (ref "P10") (pin "8") (pinfunction "187_8") (pintype "bidirectional"))
      (node (ref "U4") (pin "187") (pinfunction "IO,_RUP4_187") (pintype "bidirectional"))
    )
    (net (code "190") (name "/188") (class "Default")
      (node (ref "U4") (pin "188") (pinfunction "IO,_RDN4_188") (pintype "bidirectional"))
    )
    (net (code "191") (name "/189") (class "Default")
      (node (ref "U4") (pin "189") (pinfunction "IO_189") (pintype "bidirectional"))
    )
    (net (code "192") (name "/194") (class "Default")
      (node (ref "U4") (pin "194") (pinfunction "IO,_(PADD0),_(DQ5T)_194") (pintype "bidirectional"))
    )
    (net (code "193") (name "/195") (class "Default")
      (node (ref "U4") (pin "195") (pinfunction "IO,_VREFB7N0_195") (pintype "bidirectional"))
    )
    (net (code "194") (name "/196") (class "Default")
      (node (ref "P10") (pin "13") (pinfunction "196_13") (pintype "bidirectional"))
      (node (ref "U4") (pin "196") (pinfunction "IO,_DIFFIO_T19n,_(PADD1)_196") (pintype "bidirectional"))
    )
    (net (code "195") (name "/197") (class "Default")
      (node (ref "P10") (pin "14") (pinfunction "197_14") (pintype "bidirectional"))
      (node (ref "U4") (pin "197") (pinfunction "IO,_DIFFIO_T19p,_(PADD2),_(DQ5T)_197") (pintype "bidirectional"))
    )
    (net (code "196") (name "/200") (class "Default")
      (node (ref "U4") (pin "200") (pinfunction "IO,_(PADD4),_(DQS2T/CQ3T,DPCLK8)_200") (pintype "bidirectional"))
    )
    (net (code "197") (name "/201") (class "Default")
      (node (ref "P10") (pin "16") (pinfunction "201_16") (pintype "bidirectional"))
      (node (ref "U4") (pin "201") (pinfunction "IO,_(PADD5),_(DQ5T)_201") (pintype "bidirectional"))
    )
    (net (code "198") (name "/202") (class "Default")
      (node (ref "P10") (pin "17") (pinfunction "202_17") (pintype "bidirectional"))
      (node (ref "U4") (pin "202") (pinfunction "IO,_DIFFIO_T15n,_(PADD7),_(DQ5T)_202") (pintype "bidirectional"))
    )
    (net (code "199") (name "/203") (class "Default")
      (node (ref "P10") (pin "18") (pinfunction "203_18") (pintype "bidirectional"))
      (node (ref "U4") (pin "203") (pinfunction "IO,_DIFFIO_T15p,_(PADD8)_203") (pintype "bidirectional"))
    )
    (net (code "200") (name "/207") (class "Default")
      (node (ref "P10") (pin "19") (pinfunction "207_19") (pintype "bidirectional"))
      (node (ref "U4") (pin "207") (pinfunction "IO,_(PADD12),_(DQS4T/CQ5T,DPCLK9)_207") (pintype "bidirectional"))
    )
    (net (code "201") (name "/214") (class "Default")
      (node (ref "P10") (pin "26") (pinfunction "214_26") (pintype "bidirectional"))
      (node (ref "U4") (pin "214") (pinfunction "IO,_(PADD17),_(DQS5T/CQ5T#,DPCLK10)_214") (pintype "bidirectional"))
    )
    (net (code "202") (name "/216") (class "Default")
      (node (ref "P10") (pin "27") (pinfunction "216_27") (pintype "bidirectional"))
      (node (ref "U4") (pin "216") (pinfunction "IO_216") (pintype "bidirectional"))
    )
    (net (code "203") (name "/217") (class "Default")
      (node (ref "P10") (pin "28") (pinfunction "217_28") (pintype "bidirectional"))
      (node (ref "U4") (pin "217") (pinfunction "IO,_(DQ5T)_217") (pintype "bidirectional"))
    )
    (net (code "204") (name "/218") (class "Default")
      (node (ref "P10") (pin "29") (pinfunction "218_29") (pintype "bidirectional"))
      (node (ref "U4") (pin "218") (pinfunction "IO,_DIFFIO_T10n,_(DATA2)_218") (pintype "bidirectional"))
    )
    (net (code "205") (name "/219") (class "Default")
      (node (ref "P10") (pin "30") (pinfunction "219_30") (pintype "bidirectional"))
      (node (ref "U4") (pin "219") (pinfunction "IO,_DIFFIO_T10p,_(DATA3),_(DQ5T)_219") (pintype "bidirectional"))
    )
    (net (code "206") (name "/221") (class "Default")
      (node (ref "P10") (pin "31") (pinfunction "221_31") (pintype "bidirectional"))
      (node (ref "U4") (pin "221") (pinfunction "IO,_(DATA4),_(DQ5T)_221") (pintype "bidirectional"))
    )
    (net (code "207") (name "/223") (class "Default")
      (node (ref "P10") (pin "32") (pinfunction "223_32") (pintype "bidirectional"))
      (node (ref "U4") (pin "223") (pinfunction "IO,_VREFB8N0_223") (pintype "bidirectional"))
    )
    (net (code "208") (name "/224") (class "Default")
      (node (ref "P10") (pin "33") (pinfunction "224_33") (pintype "bidirectional"))
      (node (ref "U4") (pin "224") (pinfunction "IO,_(DATA14),_(DQS3T/CQ3T#,DPCLK11)_224") (pintype "bidirectional"))
    )
    (net (code "209") (name "/226") (class "Default")
      (node (ref "P10") (pin "34") (pinfunction "226_34") (pintype "bidirectional"))
      (node (ref "U4") (pin "226") (pinfunction "IO,_(DATA5),_(DQ5T)_226") (pintype "bidirectional"))
    )
    (net (code "210") (name "/230") (class "Default")
      (node (ref "P10") (pin "35") (pinfunction "230_35") (pintype "bidirectional"))
      (node (ref "U4") (pin "230") (pinfunction "IO,_DIFFIO_T6n_230") (pintype "bidirectional"))
    )
    (net (code "211") (name "/231") (class "Default")
      (node (ref "P10") (pin "36") (pinfunction "231_36") (pintype "bidirectional"))
      (node (ref "U4") (pin "231") (pinfunction "IO,_DIFFIO_T6p,_(DATA6),_(DQ5T)_231") (pintype "bidirectional"))
    )
    (net (code "212") (name "/232") (class "Default")
      (node (ref "P10") (pin "37") (pinfunction "232_37") (pintype "bidirectional"))
      (node (ref "U4") (pin "232") (pinfunction "IO,_(DATA7),_(DM5T/BWS#5T)_232") (pintype "bidirectional"))
    )
    (net (code "213") (name "/233") (class "Default")
      (node (ref "P10") (pin "38") (pinfunction "233_38") (pintype "bidirectional"))
      (node (ref "U4") (pin "233") (pinfunction "IO,_(DATA11)_233") (pintype "bidirectional"))
    )
    (net (code "214") (name "/234") (class "Default")
      (node (ref "P10") (pin "39") (pinfunction "234_39") (pintype "bidirectional"))
      (node (ref "U4") (pin "234") (pinfunction "IO,_DIFFIO_T2n_234") (pintype "bidirectional"))
    )
    (net (code "215") (name "/235") (class "Default")
      (node (ref "P10") (pin "40") (pinfunction "235_40") (pintype "bidirectional"))
      (node (ref "U4") (pin "235") (pinfunction "IO,_DIFFIO_T2p_235") (pintype "bidirectional"))
    )
    (net (code "216") (name "/236") (class "Default")
      (node (ref "P10") (pin "41") (pinfunction "236_41") (pintype "bidirectional"))
      (node (ref "U4") (pin "236") (pinfunction "IO,_(DATA12),_(DQS1T/CQ1T#,CDPCLK7)_236") (pintype "bidirectional"))
    )
    (net (code "217") (name "/237") (class "Default")
      (node (ref "P10") (pin "42") (pinfunction "237_42") (pintype "bidirectional"))
      (node (ref "U4") (pin "237") (pinfunction "IO,_DIFFIO_T1n_237") (pintype "bidirectional"))
    )
    (net (code "218") (name "/238") (class "Default")
      (node (ref "P10") (pin "43") (pinfunction "238_43") (pintype "bidirectional"))
      (node (ref "U4") (pin "238") (pinfunction "IO,_DIFFIO_T1p_238") (pintype "bidirectional"))
    )
    (net (code "219") (name "/239") (class "Default")
      (node (ref "P10") (pin "44") (pinfunction "239_44") (pintype "bidirectional"))
      (node (ref "U4") (pin "239") (pinfunction "IO,_PLL3_CLKOUTn_239") (pintype "bidirectional"))
    )
    (net (code "220") (name "/240") (class "Default")
      (node (ref "P10") (pin "45") (pinfunction "240_45") (pintype "bidirectional"))
      (node (ref "U4") (pin "240") (pinfunction "IO,_PLL3_CLKOUTp_240") (pintype "bidirectional"))
    )
    (net (code "221") (name "/ASDI") (class "Default")
      (node (ref "EPCS") (pin "9") (pinfunction "9_9") (pintype "passive"))
      (node (ref "U10") (pin "5") (pinfunction "5_5") (pintype "passive"))
      (node (ref "U4") (pin "12") (pinfunction "IO,_(DATA1,_ASDO)_12") (pintype "bidirectional"))
    )
    (net (code "222") (name "/CLK0") (class "Default")
      (node (ref "R21") (pin "1") (pinfunction "1_1") (pintype "passive"))
      (node (ref "U4") (pin "31") (pinfunction "CLK0,_DIFFCLK_0p_31") (pintype "input"))
    )
    (net (code "223") (name "/CLK1") (class "Default")
      (node (ref "U4") (pin "32") (pinfunction "CLK1,_DIFFCLK_0n_32") (pintype "input+no_connect"))
    )
    (net (code "224") (name "/CLK2") (class "Default")
      (node (ref "U4") (pin "33") (pinfunction "CLK2,_DIFFCLK_1p_33") (pintype "input+no_connect"))
    )
    (net (code "225") (name "/CLK3") (class "Default")
      (node (ref "U4") (pin "34") (pinfunction "CLK3,_DIFFCLK_1n_34") (pintype "input+no_connect"))
    )
    (net (code "226") (name "/CLK4") (class "Default")
      (node (ref "P10") (pin "122") (pinfunction "CLK4_122") (pintype "input"))
      (node (ref "U4") (pin "152") (pinfunction "CLK4,_DIFFCLK_2p_152") (pintype "input"))
    )
    (net (code "227") (name "/CLK5") (class "Default")
      (node (ref "P10") (pin "124") (pinfunction "CLK5_124") (pintype "input"))
      (node (ref "U4") (pin "151") (pinfunction "CLK5,_DIFFCLK_2n_151") (pintype "input"))
    )
    (net (code "228") (name "/CLK6") (class "Default")
      (node (ref "P10") (pin "123") (pinfunction "CLK6_123") (pintype "input"))
      (node (ref "U4") (pin "150") (pinfunction "CLK6,_DIFFCLK_3p_150") (pintype "input"))
    )
    (net (code "229") (name "/CLK7") (class "Default")
      (node (ref "R14") (pin "2") (pinfunction "2_2") (pintype "passive"))
      (node (ref "R15") (pin "2") (pinfunction "2_2") (pintype "passive"))
      (node (ref "U4") (pin "149") (pinfunction "CLK7,_DIFFCLK_3n_149") (pintype "input"))
    )
    (net (code "230") (name "/CLK9") (class "Default")
      (node (ref "P10") (pin "23") (pinfunction "CLK9_23") (pintype "input"))
      (node (ref "U4") (pin "210") (pinfunction "CLK9,_DIFFCLK_5p_210") (pintype "input"))
    )
    (net (code "231") (name "/CLK10") (class "Default")
      (node (ref "P10") (pin "24") (pinfunction "CLK10_24") (pintype "input"))
      (node (ref "U4") (pin "211") (pinfunction "CLK10,_DIFFCLK_4n_211") (pintype "input"))
    )
    (net (code "232") (name "/CLK11") (class "Default")
      (node (ref "P10") (pin "25") (pinfunction "CLK11_25") (pintype "input"))
      (node (ref "U4") (pin "212") (pinfunction "CLK11,_DIFFCLK_4p_212") (pintype "input"))
    )
    (net (code "233") (name "/CLK12") (class "Default")
      (node (ref "U4") (pin "92") (pinfunction "CLK12,_DIFFCLK_7n_92") (pintype "input"))
    )
    (net (code "234") (name "/CLK13") (class "Default")
      (node (ref "U4") (pin "91") (pinfunction "CLK13,_DIFFCLK_7p_91") (pintype "input"))
    )
    (net (code "235") (name "/CLK14") (class "Default")
      (node (ref "R6") (pin "1") (pinfunction "1_1") (pintype "passive"))
      (node (ref "R7") (pin "2") (pinfunction "2_2") (pintype "passive"))
      (node (ref "U4") (pin "90") (pinfunction "CLK14,_DIFFCLK_6n_90") (pintype "input"))
      (node (ref "U5") (pin "2") (pinfunction "2_2") (pintype "passive"))
    )
    (net (code "236") (name "/CLK15") (class "Default")
      (node (ref "P10") (pin "74") (pinfunction "CLK15_74") (pintype "input"))
      (node (ref "U4") (pin "89") (pinfunction "CLK15,_DIFFCLK_6p_89") (pintype "input"))
    )
    (net (code "237") (name "/CLKIN2") (class "Default")
      (node (ref "R21") (pin "2") (pinfunction "2_2") (pintype "passive"))
      (node (ref "R23") (pin "2") (pinfunction "2_2") (pintype "passive"))
    )
    (net (code "238") (name "/DATA") (class "Default")
      (node (ref "EPCS") (pin "7") (pinfunction "7_7") (pintype "passive"))
      (node (ref "U10") (pin "2") (pinfunction "2_2") (pintype "passive"))
      (node (ref "U4") (pin "24") (pinfunction "IO,_(DATA0)_24") (pintype "bidirectional"))
    )
    (net (code "239") (name "/DCLK") (class "Default")
      (node (ref "EPCS") (pin "1") (pinfunction "1_1") (pintype "passive"))
      (node (ref "R16") (pin "1") (pinfunction "1_1") (pintype "passive"))
      (node (ref "U10") (pin "6") (pinfunction "6_6") (pintype "passive"))
      (node (ref "U4") (pin "23") (pinfunction "DCLK_23") (pintype "bidirectional"))
    )
    (net (code "241") (name "/MISO") (class "Default")
      (node (ref "P10") (pin "15") (pinfunction "200_15") (pintype "bidirectional"))
    )
    (net (code "242") (name "/MOSI") (class "Default")
      (node (ref "P10") (pin "10") (pinfunction "189_10") (pintype "bidirectional"))
    )
    (net (code "243") (name "/NCE") (class "Default")
      (node (ref "EPCS") (pin "6") (pinfunction "6_6") (pintype "passive"))
      (node (ref "R20") (pin "2") (pinfunction "2_2") (pintype "passive"))
      (node (ref "U4") (pin "30") (pinfunction "nCE_30") (pintype "input"))
    )
    (net (code "244") (name "/NCONFIG") (class "Default")
      (node (ref "EPCS") (pin "5") (pinfunction "5_5") (pintype "passive"))
      (node (ref "R13") (pin "1") (pinfunction "1_1") (pintype "passive"))
      (node (ref "U4") (pin "25") (pinfunction "nCONFIG_25") (pintype "input"))
    )
    (net (code "245") (name "/NCONF_DONE") (class "Default")
      (node (ref "EPCS") (pin "3") (pinfunction "3_3") (pintype "passive"))
      (node (ref "R11") (pin "1") (pinfunction "1_1") (pintype "passive"))
      (node (ref "U4") (pin "153") (pinfunction "CONF_DONE_153") (pintype "bidirectional"))
    )
    (net (code "246") (name "/NCS") (class "Default")
      (node (ref "EPCS") (pin "8") (pinfunction "8_8") (pintype "passive"))
      (node (ref "U10") (pin "1") (pinfunction "1_1") (pintype "passive"))
      (node (ref "U4") (pin "14") (pinfunction "IO,_(FLASH_nCE,_nCSO)_14") (pintype "bidirectional"))
    )
    (net (code "247") (name "/NSTATUS") (class "Default")
      (node (ref "R12") (pin "1") (pinfunction "1_1") (pintype "passive"))
      (node (ref "U4") (pin "17") (pinfunction "nSTATUS_17") (pintype "bidirectional"))
    )
    (net (code "248") (name "/NetD0_1") (class "Default")
      (node (ref "D0") (pin "1") (pinfunction "A_1") (pintype "passive"))
      (node (ref "D1") (pin "1") (pinfunction "A_1") (pintype "passive"))
      (node (ref "R4") (pin "2") (pinfunction "2_2") (pintype "passive"))
    )
    (net (code "249") (name "/NetD2_1") (class "Default")
      (node (ref "D2") (pin "1") (pinfunction "A_1") (pintype "passive"))
      (node (ref "D3") (pin "1") (pinfunction "A_1") (pintype "passive"))
      (node (ref "R3") (pin "2") (pinfunction "2_2") (pintype "passive"))
    )
    (net (code "250") (name "/NetL4_1") (class "Default")
      (node (ref "L4") (pin "1") (pinfunction "1_1") (pintype "passive"))
      (node (ref "X1") (pin "4") (pinfunction "4_4") (pintype "passive"))
    )
    (net (code "251") (name "/NetL7_1") (class "Default")
      (node (ref "L7") (pin "1") (pinfunction "1_1") (pintype "passive"))
      (node (ref "X2") (pin "4") (pinfunction "4_4") (pintype "passive"))
    )
    (net (code "252") (name "/NetR6_2") (class "Default")
      (node (ref "R6") (pin "2") (pinfunction "2_2") (pintype "passive"))
      (node (ref "RESET") (pin "2") (pinfunction "2_2") (pintype "passive"))
      (node (ref "U5") (pin "3") (pinfunction "3_3") (pintype "passive"))
    )
    (net (code "253") (name "/NetR9_2") (class "Default")
      (node (ref "R9") (pin "2") (pinfunction "2_2") (pintype "passive"))
      (node (ref "X1") (pin "1") (pinfunction "1_1") (pintype "passive"))
    )
    (net (code "254") (name "/NetR10_2") (class "Default")
      (node (ref "R10") (pin "2") (pinfunction "2_2") (pintype "passive"))
      (node (ref "U4") (pin "157") (pinfunction "MSEL1_157") (pintype "input"))
    )
    (net (code "255") (name "/NetR14_1") (class "Default")
      (node (ref "R14") (pin "1") (pinfunction "1_1") (pintype "passive"))
      (node (ref "U4") (pin "209") (pinfunction "CLK8,_DIFFCLK_5n_209") (pintype "input"))
    )
    (net (code "256") (name "/NetR15_1") (class "Default")
      (node (ref "R15") (pin "1") (pinfunction "1_1") (pintype "passive"))
      (node (ref "X1") (pin "3") (pinfunction "3_3") (pintype "passive"))
    )
    (net (code "257") (name "/NetR22_2") (class "Default")
      (node (ref "R22") (pin "2") (pinfunction "2_2") (pintype "passive"))
      (node (ref "X2") (pin "1") (pinfunction "1_1") (pintype "passive"))
    )
    (net (code "258") (name "/NetR23_1") (class "Default")
      (node (ref "R23") (pin "1") (pinfunction "1_1") (pintype "passive"))
      (node (ref "X2") (pin "3") (pinfunction "3_3") (pintype "passive"))
    )
    (net (code "259") (name "/RES") (class "Default")
      (node (ref "P10") (pin "11") (pinfunction "194_11") (pintype "bidirectional"))
    )
    (net (code "260") (name "/SCL") (class "Default")
      (node (ref "P10") (pin "94") (pinfunction "118_94") (pintype "bidirectional"))
    )
    (net (code "261") (name "/SCLK") (class "Default")
      (node (ref "P10") (pin "9") (pinfunction "188_9") (pintype "bidirectional"))
    )
    (net (code "262") (name "/SCL_24") (class "Default")
      (node (ref "P10") (pin "84") (pinfunction "106_84") (pintype "bidirectional"))
    )
    (net (code "263") (name "/SCS") (class "Default")
      (node (ref "P10") (pin "12") (pinfunction "195_12") (pintype "bidirectional"))
    )
    (net (code "264") (name "/SDA") (class "Default")
      (node (ref "P10") (pin "93") (pinfunction "117_93") (pintype "bidirectional"))
    )
    (net (code "265") (name "/SDA_24") (class "Default")
      (node (ref "P10") (pin "86") (pinfunction "108_86") (pintype "bidirectional"))
    )
    (net (code "266") (name "/SD_A0") (class "Default")
      (node (ref "U4") (pin "94") (pinfunction "IO,_DIFFIO_B13n,_(DQ5B)_94") (pintype "bidirectional"))
    )
    (net (code "267") (name "/SD_A1") (class "Default")
      (node (ref "U4") (pin "95") (pinfunction "IO_95") (pintype "bidirectional"))
    )
    (net (code "268") (name "/SD_A2") (class "Default")
      (node (ref "U4") (pin "98") (pinfunction "IO,_DIFFIO_B16p,_(DQ5B)_98") (pintype "bidirectional"))
    )
    (net (code "269") (name "/SD_A3") (class "Default")
      (node (ref "U4") (pin "99") (pinfunction "IO,_DIFFIO_B16n,_(DQS4B/CQ5B,DPCLK4)_99") (pintype "bidirectional"))
    )
    (net (code "270") (name "/SD_A4") (class "Default")
      (node (ref "U4") (pin "84") (pinfunction "IO_84") (pintype "bidirectional"))
    )
    (net (code "271") (name "/SD_A5") (class "Default")
      (node (ref "U4") (pin "83") (pinfunction "IO,_(DQS5B/CQ5B#,DPCLK3)_83") (pintype "bidirectional"))
    )
    (net (code "272") (name "/SD_A6") (class "Default")
      (node (ref "U4") (pin "82") (pinfunction "IO,_DIFFIO_B7n,_(DQ5B)_82") (pintype "bidirectional"))
    )
    (net (code "273") (name "/SD_A7") (class "Default")
      (node (ref "U4") (pin "81") (pinfunction "IO,_DIFFIO_B7p,_(DQ5B)_81") (pintype "bidirectional"))
    )
    (net (code "274") (name "/SD_A8") (class "Default")
      (node (ref "U4") (pin "78") (pinfunction "IO,_(DQS3B/CQ3B#,DPCLK2)_78") (pintype "bidirectional"))
    )
    (net (code "275") (name "/SD_A9") (class "Default")
      (node (ref "U4") (pin "80") (pinfunction "IO,_(DM5B/BWS#5B)_80") (pintype "bidirectional"))
    )
    (net (code "276") (name "/SD_A10") (class "Default")
      (node (ref "U4") (pin "93") (pinfunction "IO,_DIFFIO_B13p,_(DQ5B)_93") (pintype "bidirectional"))
    )
    (net (code "277") (name "/SD_A11") (class "Default")
      (node (ref "U4") (pin "73") (pinfunction "IO_73") (pintype "bidirectional"))
    )
    (net (code "278") (name "/SD_DQ0") (class "Default")
      (node (ref "U4") (pin "37") (pinfunction "IO,_DIFFIO_L8p,_(DQ1L)_37") (pintype "bidirectional"))
    )
    (net (code "279") (name "/SD_DQ1") (class "Default")
      (node (ref "U4") (pin "38") (pinfunction "IO,_DIFFIO_L8n,_(DQ1L)_38") (pintype "bidirectional"))
    )
    (net (code "280") (name "/SD_DQ2") (class "Default")
      (node (ref "U4") (pin "39") (pinfunction "IO_39") (pintype "bidirectional"))
    )
    (net (code "281") (name "/SD_DQ3") (class "Default")
      (node (ref "U4") (pin "41") (pinfunction "IO,_DIFFIO_L10p,_(DQ1L)_41") (pintype "bidirectional"))
    )
    (net (code "282") (name "/SD_DQ4") (class "Default")
      (node (ref "U4") (pin "43") (pinfunction "IO,_DIFFIO_L10n,_(DQ1L)_43") (pintype "bidirectional"))
    )
    (net (code "283") (name "/SD_DQ5") (class "Default")
      (node (ref "U4") (pin "44") (pinfunction "IO,_DIFFIO_L11p,_(DQS1L/CQ1L#,DPCLK1)_44") (pintype "bidirectional"))
    )
    (net (code "284") (name "/SD_DQ6") (class "Default")
      (node (ref "U4") (pin "45") (pinfunction "IO,_DIFFIO_L11n,_(DQ1L)_45") (pintype "bidirectional"))
    )
    (net (code "285") (name "/SD_DQ7") (class "Default")
      (node (ref "U4") (pin "46") (pinfunction "IO,_VREFB2N0_46") (pintype "bidirectional"))
    )
    (net (code "286") (name "/SD_DQ14") (class "Default")
      (node (ref "U4") (pin "56") (pinfunction "IO,_DIFFIO_L15p_56") (pintype "bidirectional"))
    )
    (net (code "287") (name "/SD_DQ15") (class "Default")
      (node (ref "U4") (pin "57") (pinfunction "IO,_DIFFIO_L15n,_(DQ1L)_57") (pintype "bidirectional"))
    )
    (net (code "288") (name "/TCK") (class "Default")
      (node (ref "JTAG") (pin "1") (pinfunction "1_1") (pintype "passive"))
      (node (ref "R19") (pin "2") (pinfunction "2_2") (pintype "passive"))
      (node (ref "U4") (pin "27") (pinfunction "TCK_27") (pintype "input"))
    )
    (net (code "289") (name "/TDI") (class "Default")
      (node (ref "JTAG") (pin "9") (pinfunction "9_9") (pintype "passive"))
      (node (ref "R17") (pin "1") (pinfunction "1_1") (pintype "passive"))
      (node (ref "U4") (pin "26") (pinfunction "TDI_26") (pintype "input"))
    )
    (net (code "290") (name "/TDO") (class "Default")
      (node (ref "JTAG") (pin "3") (pinfunction "3_3") (pintype "passive"))
      (node (ref "U4") (pin "29") (pinfunction "TDO_29") (pintype "output"))
    )
    (net (code "291") (name "/TMS") (class "Default")
      (node (ref "JTAG") (pin "5") (pinfunction "5_5") (pintype "passive"))
      (node (ref "R18") (pin "1") (pinfunction "1_1") (pintype "passive"))
      (node (ref "U4") (pin "28") (pinfunction "TMS_28") (pintype "input"))
    )
    (net (code "292") (name "/VCC_1.2") (class "Default")
      (node (ref "C10") (pin "2") (pinfunction "2_2") (pintype "passive"))
      (node (ref "C12") (pin "2") (pinfunction "2_2") (pintype "passive"))
      (node (ref "C14") (pin "2") (pinfunction "2_2") (pintype "passive"))
      (node (ref "C15") (pin "2") (pinfunction "2_2") (pintype "passive"))
      (node (ref "C17") (pin "2") (pinfunction "2_2") (pintype "passive"))
      (node (ref "C18") (pin "2") (pinfunction "2_2") (pintype "passive"))
      (node (ref "C27") (pin "2") (pinfunction "2_2") (pintype "passive"))
      (node (ref "C28") (pin "2") (pinfunction "2_2") (pintype "passive"))
      (node (ref "C33") (pin "2") (pinfunction "2_2") (pintype "passive"))
      (node (ref "C34") (pin "2") (pinfunction "2_2") (pintype "passive"))
      (node (ref "C37") (pin "2") (pinfunction "2_2") (pintype "passive"))
      (node (ref "C44") (pin "2") (pinfunction "2_2") (pintype "passive"))
      (node (ref "C48") (pin "2") (pinfunction "2_2") (pintype "passive"))
      (node (ref "C50") (pin "2") (pinfunction "2_2") (pintype "passive"))
      (node (ref "C51") (pin "2") (pinfunction "2_2") (pintype "passive"))
      (node (ref "C53") (pin "2") (pinfunction "2_2") (pintype "passive"))
      (node (ref "C55") (pin "2") (pinfunction "2_2") (pintype "passive"))
      (node (ref "C69") (pin "2") (pinfunction "2_2") (pintype "passive"))
      (node (ref "C7") (pin "2") (pinfunction "2_2") (pintype "passive"))
      (node (ref "C71") (pin "2") (pinfunction "2_2") (pintype "passive"))
      (node (ref "C8") (pin "2") (pinfunction "2_2") (pintype "passive"))
      (node (ref "P1") (pin "2") (pinfunction "2_2") (pintype "passive"))
      (node (ref "R2") (pin "2") (pinfunction "2_2") (pintype "passive"))
      (node (ref "U4") (pin "1") (pinfunction "VCCD_PLL3_1") (pintype "power_in"))
      (node (ref "U4") (pin "10") (pinfunction "VCCINT_10") (pintype "power_in"))
      (node (ref "U4") (pin "101") (pinfunction "VCCINT_101") (pintype "power_in"))
      (node (ref "U4") (pin "115") (pinfunction "VCCINT_115") (pintype "power_in"))
      (node (ref "U4") (pin "121") (pinfunction "VCCD_PLL4_121") (pintype "power_in"))
      (node (ref "U4") (pin "129") (pinfunction "VCCINT_129") (pintype "power_in"))
      (node (ref "U4") (pin "140") (pinfunction "VCCINT_140") (pintype "power_in"))
      (node (ref "U4") (pin "163") (pinfunction "VCCINT_163") (pintype "power_in"))
      (node (ref "U4") (pin "174") (pinfunction "VCCINT_174") (pintype "power_in"))
      (node (ref "U4") (pin "180") (pinfunction "VCCD_PLL2_180") (pintype "power_in"))
      (node (ref "U4") (pin "19") (pinfunction "VCCINT_19") (pintype "power_in"))
      (node (ref "U4") (pin "190") (pinfunction "VCCINT_190") (pintype "power_in"))
      (node (ref "U4") (pin "198") (pinfunction "VCCINT_198") (pintype "power_in"))
      (node (ref "U4") (pin "204") (pinfunction "VCCINT_204") (pintype "power_in"))
      (node (ref "U4") (pin "220") (pinfunction "VCCINT_220") (pintype "power_in"))
      (node (ref "U4") (pin "228") (pinfunction "VCCINT_228") (pintype "power_in"))
      (node (ref "U4") (pin "40") (pinfunction "VCCINT_40") (pintype "power_in"))
      (node (ref "U4") (pin "53") (pinfunction "VCCINT_53") (pintype "power_in"))
      (node (ref "U4") (pin "60") (pinfunction "VCCD_PLL1_60") (pintype "power_in"))
      (node (ref "U4") (pin "61") (pinfunction "VCCINT_61") (pintype "power_in"))
      (node (ref "U4") (pin "74") (pinfunction "VCCINT_74") (pintype "power_in"))
      (node (ref "U4") (pin "85") (pinfunction "VCCINT_85") (pintype "power_in"))
    )
    (net (code "293") (name "/VCC_2.5") (class "Default")
      (node (ref "C70") (pin "2") (pinfunction "2_2") (pintype "passive"))
      (node (ref "C72") (pin "1") (pinfunction "1_1") (pintype "passive"))
      (node (ref "L2") (pin "1") (pinfunction "1_1") (pintype "passive"))
      (node (ref "L3") (pin "1") (pinfunction "1_1") (pintype "passive"))
      (node (ref "L5") (pin "1") (pinfunction "1_1") (pintype "passive"))
      (node (ref "L6") (pin "1") (pinfunction "1_1") (pintype "passive"))
      (node (ref "U1") (pin "2") (pinfunction "2_2") (pintype "passive"))
      (node (ref "U1") (pin "4") (pinfunction "4_4") (pintype "passive"))
    )
    (net (code "294") (name "/VCC_5") (class "Default")
      (node (ref "C1") (pin "2") (pinfunction "2_2") (pintype "passive"))
      (node (ref "C3") (pin "1") (pinfunction "1_1") (pintype "passive"))
      (node (ref "C4") (pin "1") (pinfunction "1_1") (pintype "passive"))
      (node (ref "P1") (pin "3") (pinfunction "3_3") (pintype "passive"))
      (node (ref "P10") (pin "1") (pinfunction "VCC_5_1") (pintype "power_in"))
      (node (ref "P10") (pin "149") (pinfunction "VCC_5_149") (pintype "power_in"))
      (node (ref "R1") (pin "2") (pinfunction "2_2") (pintype "passive"))
      (node (ref "SW") (pin "2") (pinfunction "2_2") (pintype "passive"))
      (node (ref "U1") (pin "3") (pinfunction "3_3") (pintype "passive"))
      (node (ref "U2") (pin "3") (pinfunction "3_3") (pintype "passive"))
    )
    (net (code "295") (name "/VCC_PLL1") (class "Default")
      (node (ref "C38") (pin "2") (pinfunction "2_2") (pintype "passive"))
      (node (ref "C39") (pin "2") (pinfunction "2_2") (pintype "passive"))
      (node (ref "C40") (pin "1") (pinfunction "1_1") (pintype "passive"))
      (node (ref "L5") (pin "2") (pinfunction "2_2") (pintype "passive"))
      (node (ref "U4") (pin "58") (pinfunction "VCCA1_58") (pintype "power_in"))
    )
    (net (code "296") (name "/VCC_PLL2") (class "Default")
      (node (ref "C25") (pin "2") (pinfunction "2_2") (pintype "passive"))
      (node (ref "C26") (pin "2") (pinfunction "2_2") (pintype "passive"))
      (node (ref "C30") (pin "1") (pinfunction "1_1") (pintype "passive"))
      (node (ref "L3") (pin "2") (pinfunction "2_2") (pintype "passive"))
      (node (ref "U4") (pin "178") (pinfunction "VCCA2_178") (pintype "power_in"))
    )
    (net (code "297") (name "/VCC_PLL3") (class "Default")
      (node (ref "C23") (pin "2") (pinfunction "2_2") (pintype "passive"))
      (node (ref "C24") (pin "2") (pinfunction "2_2") (pintype "passive"))
      (node (ref "C29") (pin "1") (pinfunction "1_1") (pintype "passive"))
      (node (ref "L2") (pin "2") (pinfunction "2_2") (pintype "passive"))
      (node (ref "U4") (pin "3") (pinfunction "VCCA3_3") (pintype "power_in"))
    )
    (net (code "298") (name "/VCC_PLL4") (class "Default")
      (node (ref "C41") (pin "1") (pinfunction "1_1") (pintype "passive"))
      (node (ref "C42") (pin "2") (pinfunction "2_2") (pintype "passive"))
      (node (ref "C43") (pin "2") (pinfunction "2_2") (pintype "passive"))
      (node (ref "L6") (pin "2") (pinfunction "2_2") (pintype "passive"))
      (node (ref "U4") (pin "123") (pinfunction "VCCA4_123") (pintype "power_in"))
    )
    (net (code "299") (name "GND") (class "Default")
      (node (ref "32_PWR") (pin "2") (pinfunction "K_2") (pintype "passive"))
      (node (ref "32_RESET") (pin "2") (pinfunction "2_2") (pintype "passive"))
      (node (ref "C1") (pin "1") (pinfunction "1_1") (pintype "passive"))
      (node (ref "C10") (pin "1") (pinfunction "1_1") (pintype "passive"))
      (node (ref "C11") (pin "1") (pinfunction "1_1") (pintype "passive"))
      (node (ref "C12") (pin "1") (pinfunction "1_1") (pintype "passive"))
      (node (ref "C13") (pin "1") (pinfunction "1_1") (pintype "passive"))
      (node (ref "C14") (pin "1") (pinfunction "1_1") (pintype "passive"))
      (node (ref "C15") (pin "1") (pinfunction "1_1") (pintype "passive"))
      (node (ref "C16") (pin "1") (pinfunction "1_1") (pintype "passive"))
      (node (ref "C17") (pin "1") (pinfunction "1_1") (pintype "passive"))
      (node (ref "C18") (pin "1") (pinfunction "1_1") (pintype "passive"))
      (node (ref "C19") (pin "1") (pinfunction "1_1") (pintype "passive"))
      (node (ref "C2") (pin "1") (pinfunction "1_1") (pintype "passive"))
      (node (ref "C20") (pin "1") (pinfunction "1_1") (pintype "passive"))
      (node (ref "C21") (pin "1") (pinfunction "1_1") (pintype "passive"))
      (node (ref "C22") (pin "1") (pinfunction "1_1") (pintype "passive"))
      (node (ref "C23") (pin "1") (pinfunction "1_1") (pintype "passive"))
      (node (ref "C24") (pin "1") (pinfunction "1_1") (pintype "passive"))
      (node (ref "C25") (pin "1") (pinfunction "1_1") (pintype "passive"))
      (node (ref "C26") (pin "1") (pinfunction "1_1") (pintype "passive"))
      (node (ref "C27") (pin "1") (pinfunction "1_1") (pintype "passive"))
      (node (ref "C28") (pin "1") (pinfunction "1_1") (pintype "passive"))
      (node (ref "C29") (pin "2") (pinfunction "2_2") (pintype "passive"))
      (node (ref "C3") (pin "2") (pinfunction "2_2") (pintype "passive"))
      (node (ref "C30") (pin "2") (pinfunction "2_2") (pintype "passive"))
      (node (ref "C31") (pin "1") (pinfunction "1_1") (pintype "passive"))
      (node (ref "C32") (pin "1") (pinfunction "1_1") (pintype "passive"))
      (node (ref "C33") (pin "1") (pinfunction "1_1") (pintype "passive"))
      (node (ref "C34") (pin "1") (pinfunction "1_1") (pintype "passive"))
      (node (ref "C35") (pin "1") (pinfunction "1_1") (pintype "passive"))
      (node (ref "C36") (pin "1") (pinfunction "1_1") (pintype "passive"))
      (node (ref "C37") (pin "1") (pinfunction "1_1") (pintype "passive"))
      (node (ref "C38") (pin "1") (pinfunction "1_1") (pintype "passive"))
      (node (ref "C39") (pin "1") (pinfunction "1_1") (pintype "passive"))
      (node (ref "C4") (pin "2") (pinfunction "2_2") (pintype "passive"))
      (node (ref "C40") (pin "2") (pinfunction "2_2") (pintype "passive"))
      (node (ref "C41") (pin "2") (pinfunction "2_2") (pintype "passive"))
      (node (ref "C42") (pin "1") (pinfunction "1_1") (pintype "passive"))
      (node (ref "C43") (pin "1") (pinfunction "1_1") (pintype "passive"))
      (node (ref "C44") (pin "1") (pinfunction "1_1") (pintype "passive"))
      (node (ref "C45") (pin "1") (pinfunction "1_1") (pintype "passive"))
      (node (ref "C46") (pin "1") (pinfunction "1_1") (pintype "passive"))
      (node (ref "C47") (pin "1") (pinfunction "1_1") (pintype "passive"))
      (node (ref "C48") (pin "1") (pinfunction "1_1") (pintype "passive"))
      (node (ref "C49") (pin "1") (pinfunction "1_1") (pintype "passive"))
      (node (ref "C5") (pin "1") (pinfunction "1_1") (pintype "passive"))
      (node (ref "C50") (pin "1") (pinfunction "1_1") (pintype "passive"))
      (node (ref "C51") (pin "1") (pinfunction "1_1") (pintype "passive"))
      (node (ref "C52") (pin "1") (pinfunction "1_1") (pintype "passive"))
      (node (ref "C53") (pin "1") (pinfunction "1_1") (pintype "passive"))
      (node (ref "C54") (pin "1") (pinfunction "1_1") (pintype "passive"))
      (node (ref "C55") (pin "1") (pinfunction "1_1") (pintype "passive"))
      (node (ref "C56") (pin "1") (pinfunction "1_1") (pintype "passive"))
      (node (ref "C57") (pin "1") (pinfunction "1_1") (pintype "passive"))
      (node (ref "C58") (pin "1") (pinfunction "1_1") (pintype "passive"))
      (node (ref "C59") (pin "1") (pinfunction "1_1") (pintype "passive"))
      (node (ref "C6") (pin "1") (pinfunction "1_1") (pintype "passive"))
      (node (ref "C60") (pin "2") (pinfunction "2_2") (pintype "passive"))
      (node (ref "C61") (pin "2") (pinfunction "2_2") (pintype "passive"))
      (node (ref "C62") (pin "1") (pinfunction "1_1") (pintype "passive"))
      (node (ref "C63") (pin "1") (pinfunction "1_1") (pintype "passive"))
      (node (ref "C64") (pin "1") (pinfunction "1_1") (pintype "passive"))
      (node (ref "C65") (pin "1") (pinfunction "1_1") (pintype "passive"))
      (node (ref "C66") (pin "1") (pinfunction "1_1") (pintype "passive"))
      (node (ref "C67") (pin "1") (pinfunction "1_1") (pintype "passive"))
      (node (ref "C69") (pin "1") (pinfunction "1_1") (pintype "passive"))
      (node (ref "C7") (pin "1") (pinfunction "1_1") (pintype "passive"))
      (node (ref "C70") (pin "1") (pinfunction "1_1") (pintype "passive"))
      (node (ref "C71") (pin "1") (pinfunction "1_1") (pintype "passive"))
      (node (ref "C72") (pin "2") (pinfunction "2_2") (pintype "passive"))
      (node (ref "C73") (pin "1") (pinfunction "1_1") (pintype "passive"))
      (node (ref "C74") (pin "2") (pinfunction "2_2") (pintype "passive"))
      (node (ref "C77") (pin "1") (pinfunction "1_1") (pintype "passive"))
      (node (ref "C8") (pin "1") (pinfunction "1_1") (pintype "passive"))
      (node (ref "C80") (pin "1") (pinfunction "1_1") (pintype "passive"))
      (node (ref "C9") (pin "1") (pinfunction "1_1") (pintype "passive"))
      (node (ref "EPCS") (pin "10") (pinfunction "10_10") (pintype "passive"))
      (node (ref "EPCS") (pin "2") (pinfunction "2_2") (pintype "passive"))
      (node (ref "JTAG") (pin "10") (pinfunction "10_10") (pintype "passive"))
      (node (ref "JTAG") (pin "2") (pinfunction "2_2") (pintype "passive"))
      (node (ref "P1") (pin "1") (pinfunction "1_1") (pintype "passive"))
      (node (ref "P10") (pin "150") (pinfunction "GND_150") (pintype "power_in"))
      (node (ref "P10") (pin "22") (pinfunction "GND_22") (pintype "power_in"))
      (node (ref "P10") (pin "51") (pinfunction "GND_51") (pintype "power_in"))
      (node (ref "P10") (pin "53") (pinfunction "GND_53") (pintype "power_in"))
      (node (ref "P10") (pin "54") (pinfunction "GND_54") (pintype "power_in"))
      (node (ref "P10") (pin "97") (pinfunction "GND_97") (pintype "power_in"))
      (node (ref "P2") (pin "2") (pinfunction "2_2") (pintype "passive"))
      (node (ref "P2") (pin "7") (pinfunction "7_7") (pintype "passive"))
      (node (ref "PW") (pin "2") (pinfunction "2_2") (pintype "passive"))
      (node (ref "PW") (pin "3") (pinfunction "3_3") (pintype "passive"))
      (node (ref "PWLED") (pin "2") (pinfunction "K_2") (pintype "passive"))
      (node (ref "R19") (pin "1") (pinfunction "1_1") (pintype "passive"))
      (node (ref "R2") (pin "1") (pinfunction "1_1") (pintype "passive"))
      (node (ref "R20") (pin "1") (pinfunction "1_1") (pintype "passive"))
      (node (ref "R32") (pin "2") (pinfunction "2_2") (pintype "passive"))
      (node (ref "R38") (pin "1") (pinfunction "1_1") (pintype "passive"))
      (node (ref "R39") (pin "2") (pinfunction "2_2") (pintype "passive"))
      (node (ref "RESET") (pin "1") (pinfunction "1_1") (pintype "passive"))
      (node (ref "U1") (pin "1") (pinfunction "1_1") (pintype "passive"))
      (node (ref "U10") (pin "4") (pinfunction "4_4") (pintype "passive"))
      (node (ref "U13") (pin "107") (pinfunction "VSS_107") (pintype "passive"))
      (node (ref "U13") (pin "120") (pinfunction "VSS_120") (pintype "passive"))
      (node (ref "U13") (pin "130") (pinfunction "VSS_130") (pintype "passive"))
      (node (ref "U13") (pin "16") (pinfunction "VSS_16") (pintype "passive"))
      (node (ref "U13") (pin "31") (pinfunction "VSSA_31") (pintype "passive"))
      (node (ref "U13") (pin "38") (pinfunction "VSS_38") (pintype "passive"))
      (node (ref "U13") (pin "51") (pinfunction "VSS_51") (pintype "passive"))
      (node (ref "U13") (pin "61") (pinfunction "VSS_61") (pintype "passive"))
      (node (ref "U13") (pin "83") (pinfunction "VSS_83") (pintype "passive"))
      (node (ref "U13") (pin "94") (pinfunction "VSS_94") (pintype "passive"))
      (node (ref "U2") (pin "1") (pinfunction "1_1") (pintype "passive"))
      (node (ref "U3") (pin "6") (pinfunction "VSS_6") (pintype "passive"))
      (node (ref "U4") (pin "102") (pinfunction "GND_102") (pintype "power_in"))
      (node (ref "U4") (pin "105") (pinfunction "GND_105") (pintype "power_in"))
      (node (ref "U4") (pin "11") (pinfunction "GND_11") (pintype "power_in"))
      (node (ref "U4") (pin "116") (pinfunction "GND_116") (pintype "power_in"))
      (node (ref "U4") (pin "122") (pinfunction "GNDA4_122") (pintype "power_in"))
      (node (ref "U4") (pin "125") (pinfunction "GND_125") (pintype "power_in"))
      (node (ref "U4") (pin "130") (pinfunction "GND_130") (pintype "power_in"))
      (node (ref "U4") (pin "138") (pinfunction "GND_138") (pintype "power_in"))
      (node (ref "U4") (pin "141") (pinfunction "GND_141") (pintype "power_in"))
      (node (ref "U4") (pin "155") (pinfunction "MSEL0_155") (pintype "input"))
      (node (ref "U4") (pin "156") (pinfunction "GND_156") (pintype "power_in"))
      (node (ref "U4") (pin "158") (pinfunction "MSEL2_158") (pintype "input"))
      (node (ref "U4") (pin "16") (pinfunction "GND_16") (pintype "power_in"))
      (node (ref "U4") (pin "165") (pinfunction "GND_165") (pintype "power_in"))
      (node (ref "U4") (pin "172") (pinfunction "GND_172") (pintype "power_in"))
      (node (ref "U4") (pin "175") (pinfunction "GND_175") (pintype "power_in"))
      (node (ref "U4") (pin "179") (pinfunction "GNDA2_179") (pintype "power_in"))
      (node (ref "U4") (pin "191") (pinfunction "GND_191") (pintype "power_in"))
      (node (ref "U4") (pin "193") (pinfunction "GND_193") (pintype "power_in"))
      (node (ref "U4") (pin "199") (pinfunction "GND_199") (pintype "power_in"))
      (node (ref "U4") (pin "2") (pinfunction "GNDA3_2") (pintype "power_in"))
      (node (ref "U4") (pin "20") (pinfunction "GND_20") (pintype "power_in"))
      (node (ref "U4") (pin "205") (pinfunction "GND_205") (pintype "power_in"))
      (node (ref "U4") (pin "208") (pinfunction "GND_208") (pintype "power_in"))
      (node (ref "U4") (pin "215") (pinfunction "GND_215") (pintype "power_in"))
      (node (ref "U4") (pin "222") (pinfunction "GND_222") (pintype "power_in"))
      (node (ref "U4") (pin "227") (pinfunction "GND_227") (pintype "power_in"))
      (node (ref "U4") (pin "229") (pinfunction "GND_229") (pintype "power_in"))
      (node (ref "U4") (pin "36") (pinfunction "GND_36") (pintype "power_in"))
      (node (ref "U4") (pin "42") (pinfunction "GND_42") (pintype "power_in"))
      (node (ref "U4") (pin "48") (pinfunction "GND_48") (pintype "power_in"))
      (node (ref "U4") (pin "54") (pinfunction "GND_54") (pintype "power_in"))
      (node (ref "U4") (pin "59") (pinfunction "GNDA1_59") (pintype "power_in"))
      (node (ref "U4") (pin "62") (pinfunction "GND_62") (pintype "power_in"))
      (node (ref "U4") (pin "67") (pinfunction "GND_67") (pintype "power_in"))
      (node (ref "U4") (pin "75") (pinfunction "GND_75") (pintype "power_in"))
      (node (ref "U4") (pin "79") (pinfunction "GND_79") (pintype "power_in"))
      (node (ref "U4") (pin "8") (pinfunction "GND_8") (pintype "power_in"))
      (node (ref "U4") (pin "86") (pinfunction "GND_86") (pintype "power_in"))
      (node (ref "U4") (pin "97") (pinfunction "GND_97") (pintype "power_in"))
      (node (ref "U5") (pin "1") (pinfunction "1_1") (pintype "passive"))
      (node (ref "U7") (pin "6") (pinfunction "GND_6") (pintype "passive"))
      (node (ref "X1") (pin "2") (pinfunction "2_2") (pintype "passive"))
      (node (ref "X2") (pin "2") (pinfunction "2_2") (pintype "passive"))
    )
    (net (code "300") (name "Net-(32_PWR-A)") (class "Default")
      (node (ref "32_PWR") (pin "1") (pinfunction "A_1") (pintype "passive"))
      (node (ref "R42") (pin "1") (pinfunction "1_1") (pintype "passive"))
    )
    (net (code "301") (name "Net-(D4-A)") (class "Default")
      (node (ref "D4") (pin "1") (pinfunction "A_1") (pintype "passive"))
      (node (ref "R40") (pin "1") (pinfunction "1_1") (pintype "passive"))
    )
    (net (code "302") (name "Net-(D6-A)") (class "Default")
      (node (ref "D6") (pin "1") (pinfunction "A_1") (pintype "passive"))
      (node (ref "R41") (pin "1") (pinfunction "1_1") (pintype "passive"))
    )
    (net (code "303") (name "Net-(PW-Pad1)") (class "Default")
      (node (ref "PW") (pin "1") (pinfunction "1_1") (pintype "passive"))
      (node (ref "SW") (pin "1") (pinfunction "1_1") (pintype "passive"))
    )
    (net (code "304") (name "Net-(PWLED-A)") (class "Default")
      (node (ref "PWLED") (pin "1") (pinfunction "A_1") (pintype "passive"))
      (node (ref "R1") (pin "1") (pinfunction "1_1") (pintype "passive"))
    )
    (net (code "305") (name "Net-(U13-PH0-OSC_IN)") (class "Default")
      (node (ref "C59") (pin "2") (pinfunction "2_2") (pintype "passive"))
      (node (ref "R24") (pin "2") (pinfunction "2_2") (pintype "passive"))
      (node (ref "U13") (pin "23") (pinfunction "PH0-OSC_IN_23") (pintype "passive"))
      (node (ref "X4") (pin "2") (pinfunction "OSC2_2") (pintype "passive"))
    )
    (net (code "306") (name "Net-(U13-PH1-OSC_OUT)") (class "Default")
      (node (ref "C58") (pin "2") (pinfunction "2_2") (pintype "passive"))
      (node (ref "R24") (pin "1") (pinfunction "1_1") (pintype "passive"))
      (node (ref "U13") (pin "24") (pinfunction "PH1-OSC_OUT_24") (pintype "passive"))
      (node (ref "X4") (pin "1") (pinfunction "OSC1_1") (pintype "passive"))
    )
    (net (code "307") (name "Net-(U13-VDDA)") (class "Default")
      (node (ref "C62") (pin "2") (pinfunction "2_2") (pintype "passive"))
      (node (ref "C63") (pin "2") (pinfunction "2_2") (pintype "passive"))
      (node (ref "R25") (pin "1") (pinfunction "1_1") (pintype "passive"))
      (node (ref "U13") (pin "33") (pinfunction "VDDA_33") (pintype "passive"))
    )
    (net (code "308") (name "Net-(U13-Vcap_1)") (class "Default")
      (node (ref "C60") (pin "1") (pinfunction "1_1") (pintype "passive"))
      (node (ref "U13") (pin "71") (pinfunction "Vcap_1_71") (pintype "passive"))
    )
    (net (code "309") (name "Net-(U13-Vcap_2)") (class "Default")
      (node (ref "C61") (pin "1") (pinfunction "1_1") (pintype "passive"))
      (node (ref "U13") (pin "106") (pinfunction "Vcap_2_106") (pintype "passive"))
    )
    (net (code "310") (name "unconnected-(JTAG-Pad6)") (class "Default")
      (node (ref "JTAG") (pin "6") (pinfunction "6_6") (pintype "passive+no_connect"))
    )
    (net (code "311") (name "unconnected-(JTAG-Pad7)") (class "Default")
      (node (ref "JTAG") (pin "7") (pinfunction "7_7") (pintype "passive+no_connect"))
    )
    (net (code "312") (name "unconnected-(JTAG-Pad8)") (class "Default")
      (node (ref "JTAG") (pin "8") (pinfunction "8_8") (pintype "passive+no_connect"))
    )
    (net (code "313") (name "unconnected-(P2-Pad5)") (class "Default")
      (node (ref "P2") (pin "5") (pinfunction "5_5") (pintype "passive"))
    )
    (net (code "314") (name "unconnected-(P2-Pad6)") (class "Default")
      (node (ref "P2") (pin "6") (pinfunction "6_6") (pintype "passive"))
    )
    (net (code "315") (name "unconnected-(P2-Pad8)") (class "Default")
      (node (ref "P2") (pin "8") (pinfunction "8_8") (pintype "passive"))
    )
    (net (code "316") (name "unconnected-(P10-PadNC)") (class "Default")
      (node (ref "P10") (pin "NC") (pintype "passive+no_connect"))
    )
    (net (code "317") (name "unconnected-(P10-PadNC)_1") (class "Default")
      (node (ref "P10") (pin "NC") (pintype "passive+no_connect"))
    )
    (net (code "318") (name "unconnected-(P10-PadNC)_2") (class "Default")
      (node (ref "P10") (pin "NC") (pintype "passive+no_connect"))
    )
    (net (code "319") (name "unconnected-(P10-PadNC)_3") (class "Default")
      (node (ref "P10") (pin "NC") (pintype "passive+no_connect"))
    )
    (net (code "320") (name "unconnected-(P10-PadNC)_4") (class "Default")
      (node (ref "P10") (pin "NC") (pintype "passive+no_connect"))
    )
    (net (code "321") (name "unconnected-(P10-PadNC)_5") (class "Default")
      (node (ref "P10") (pin "NC") (pintype "passive+no_connect"))
    )
    (net (code "322") (name "unconnected-(P10A-6-Pad46)") (class "Default")
      (node (ref "P10") (pin "46") (pinfunction "6_46") (pintype "bidirectional+no_connect"))
    )
    (net (code "323") (name "unconnected-(P10A-VCC_2.5-Pad49)") (class "Default")
      (node (ref "P10") (pin "49") (pinfunction "VCC_2.5_49") (pintype "power_in+no_connect"))
    )
    (net (code "324") (name "unconnected-(P10A-VCC_2.5-Pad50)") (class "Default")
      (node (ref "P10") (pin "50") (pinfunction "VCC_2.5_50") (pintype "power_in+no_connect"))
    )
    (net (code "325") (name "unconnected-(P10B-63-Pad55)") (class "Default")
      (node (ref "P10") (pin "55") (pinfunction "63_55") (pintype "bidirectional+no_connect"))
    )
    (net (code "326") (name "unconnected-(P10B-64-PadNC)") (class "Default")
      (node (ref "P10") (pin "NC") (pinfunction "64_NC") (pintype "passive+no_connect"))
    )
    (net (code "327") (name "unconnected-(P10B-65-PadNC)") (class "Default")
      (node (ref "P10") (pin "NC") (pinfunction "65_NC") (pintype "passive+no_connect"))
    )
    (net (code "328") (name "unconnected-(P10B-68-PadNC)") (class "Default")
      (node (ref "P10") (pin "NC") (pinfunction "68_NC") (pintype "passive+no_connect"))
    )
    (net (code "329") (name "unconnected-(P10B-69-PadNC)") (class "Default")
      (node (ref "P10") (pin "NC") (pinfunction "69_NC") (pintype "passive+no_connect"))
    )
    (net (code "330") (name "unconnected-(P10B-70-PadNC)") (class "Default")
      (node (ref "P10") (pin "NC") (pinfunction "70_NC") (pintype "passive+no_connect"))
    )
    (net (code "331") (name "unconnected-(P10B-71-PadNC)") (class "Default")
      (node (ref "P10") (pin "NC") (pinfunction "71_NC") (pintype "passive+no_connect"))
    )
    (net (code "332") (name "unconnected-(P10B-72-PadNC)") (class "Default")
      (node (ref "P10") (pin "NC") (pinfunction "72_NC") (pintype "passive+no_connect"))
    )
    (net (code "333") (name "unconnected-(P10B-73-PadNC)") (class "Default")
      (node (ref "P10") (pin "NC") (pinfunction "73_NC") (pintype "passive+no_connect"))
    )
    (net (code "334") (name "unconnected-(P10B-76-PadNC)") (class "Default")
      (node (ref "P10") (pin "NC") (pinfunction "76_NC") (pintype "passive+no_connect"))
    )
    (net (code "335") (name "unconnected-(P10B-78-PadNC)") (class "Default")
      (node (ref "P10") (pin "NC") (pinfunction "78_NC") (pintype "passive+no_connect"))
    )
    (net (code "336") (name "unconnected-(P10B-80-PadNC)") (class "Default")
      (node (ref "P10") (pin "NC") (pinfunction "80_NC") (pintype "passive+no_connect"))
    )
    (net (code "337") (name "unconnected-(P10B-81-PadNC)") (class "Default")
      (node (ref "P10") (pin "NC") (pinfunction "81_NC") (pintype "passive+no_connect"))
    )
    (net (code "338") (name "unconnected-(P10B-82-PadNC)") (class "Default")
      (node (ref "P10") (pin "NC") (pinfunction "82_NC") (pintype "passive+no_connect"))
    )
    (net (code "339") (name "unconnected-(P10B-83-PadNC)") (class "Default")
      (node (ref "P10") (pin "NC") (pinfunction "83_NC") (pintype "passive+no_connect"))
    )
    (net (code "340") (name "unconnected-(P10B-84-PadNC)") (class "Default")
      (node (ref "P10") (pin "NC") (pinfunction "84_NC") (pintype "passive+no_connect"))
    )
    (net (code "341") (name "unconnected-(P10B-87-PadNC)") (class "Default")
      (node (ref "P10") (pin "NC") (pinfunction "87_NC") (pintype "passive+no_connect"))
    )
    (net (code "342") (name "unconnected-(P10B-88-PadNC)") (class "Default")
      (node (ref "P10") (pin "NC") (pinfunction "88_NC") (pintype "passive+no_connect"))
    )
    (net (code "343") (name "unconnected-(P10B-88-PadNC)_1") (class "Default")
      (node (ref "P10") (pin "NC") (pinfunction "88_NC") (pintype "passive+no_connect"))
    )
    (net (code "344") (name "unconnected-(P10B-93-PadNC)") (class "Default")
      (node (ref "P10") (pin "NC") (pinfunction "93_NC") (pintype "passive+no_connect"))
    )
    (net (code "345") (name "unconnected-(P10B-94-PadNC)") (class "Default")
      (node (ref "P10") (pin "NC") (pinfunction "94_NC") (pintype "passive+no_connect"))
    )
    (net (code "346") (name "unconnected-(P10B-95-PadNC)") (class "Default")
      (node (ref "P10") (pin "NC") (pinfunction "95_NC") (pintype "passive+no_connect"))
    )
    (net (code "347") (name "unconnected-(P10B-99-PadNC)") (class "Default")
      (node (ref "P10") (pin "NC") (pinfunction "99_NC") (pintype "passive+no_connect"))
    )
    (net (code "348") (name "unconnected-(P10B-109-Pad87)") (class "Default")
      (node (ref "P10") (pin "87") (pinfunction "109_87") (pintype "bidirectional+no_connect"))
    )
    (net (code "349") (name "unconnected-(P10B-113-PadNC)") (class "Default")
      (node (ref "P10") (pin "NC") (pinfunction "113_NC") (pintype "passive+no_connect"))
    )
    (net (code "350") (name "unconnected-(P10B-CLK12-PadNC)") (class "Default")
      (node (ref "P10") (pin "NC") (pinfunction "CLK12_NC") (pintype "passive+no_connect"))
    )
    (net (code "351") (name "unconnected-(P10B-CLK13-Pad76)") (class "Default")
      (node (ref "P10") (pin "76") (pinfunction "CLK13_76") (pintype "input"))
    )
    (net (code "352") (name "unconnected-(P10B-CLK14-PadNC)") (class "Default")
      (node (ref "P10") (pin "NC") (pinfunction "CLK14_NC") (pintype "passive+no_connect"))
    )
    (net (code "353") (name "unconnected-(P10C-103-PadNC)") (class "Default")
      (node (ref "P10") (pin "NC") (pinfunction "103_NC") (pintype "passive+no_connect"))
    )
    (net (code "354") (name "unconnected-(P10C-107-PadNC)") (class "Default")
      (node (ref "P10") (pin "NC") (pinfunction "107_NC") (pintype "passive"))
    )
    (net (code "355") (name "unconnected-(P10C-108-PadNC)") (class "Default")
      (node (ref "P10") (pin "NC") (pinfunction "108_NC") (pintype "passive"))
    )
    (net (code "356") (name "unconnected-(P10C-109-PadNC)") (class "Default")
      (node (ref "P10") (pin "NC") (pinfunction "109_NC") (pintype "passive"))
    )
    (net (code "357") (name "unconnected-(P10C-110-PadNC)") (class "Default")
      (node (ref "P10") (pin "NC") (pinfunction "110_NC") (pintype "passive"))
    )
    (net (code "358") (name "unconnected-(P10C-111-PadNC)") (class "Default")
      (node (ref "P10") (pin "NC") (pinfunction "111_NC") (pintype "passive"))
    )
    (net (code "359") (name "unconnected-(P10C-112-PadNC)") (class "Default")
      (node (ref "P10") (pin "NC") (pinfunction "112_NC") (pintype "passive"))
    )
    (net (code "360") (name "unconnected-(P10C-113-PadNC)") (class "Default")
      (node (ref "P10") (pin "NC") (pinfunction "113_NC") (pintype "passive"))
    )
    (net (code "361") (name "unconnected-(P10C-114-PadNC)") (class "Default")
      (node (ref "P10") (pin "NC") (pinfunction "114_NC") (pintype "passive"))
    )
    (net (code "362") (name "unconnected-(P10C-117-PadNC)") (class "Default")
      (node (ref "P10") (pin "NC") (pinfunction "117_NC") (pintype "passive"))
    )
    (net (code "363") (name "unconnected-(P10C-118-PadNC)") (class "Default")
      (node (ref "P10") (pin "NC") (pinfunction "118_NC") (pintype "passive"))
    )
    (net (code "364") (name "unconnected-(P10C-119-PadNC)") (class "Default")
      (node (ref "P10") (pin "NC") (pinfunction "119_NC") (pintype "passive"))
    )
    (net (code "365") (name "unconnected-(P10C-120-PadNC)") (class "Default")
      (node (ref "P10") (pin "NC") (pinfunction "120_NC") (pintype "passive"))
    )
    (net (code "366") (name "unconnected-(P10C-181-PadNC)") (class "Default")
      (node (ref "P10") (pin "NC") (pinfunction "181_NC") (pintype "passive+no_connect"))
    )
    (net (code "367") (name "unconnected-(P10C-182-PadNC)") (class "Default")
      (node (ref "P10") (pin "NC") (pinfunction "182_NC") (pintype "passive+no_connect"))
    )
    (net (code "368") (name "unconnected-(P10C-183-PadNC)") (class "Default")
      (node (ref "P10") (pin "NC") (pinfunction "183_NC") (pintype "passive+no_connect"))
    )
    (net (code "369") (name "unconnected-(P10C-184-PadNC)") (class "Default")
      (node (ref "P10") (pin "NC") (pinfunction "184_NC") (pintype "passive+no_connect"))
    )
    (net (code "370") (name "unconnected-(P10C-185-PadNC)") (class "Default")
      (node (ref "P10") (pin "NC") (pinfunction "185_NC") (pintype "passive+no_connect"))
    )
    (net (code "371") (name "unconnected-(P10C-187-PadNC)") (class "Default")
      (node (ref "P10") (pin "NC") (pinfunction "187_NC") (pintype "passive+no_connect"))
    )
    (net (code "372") (name "unconnected-(P10C-188-PadNC)") (class "Default")
      (node (ref "P10") (pin "NC") (pinfunction "188_NC") (pintype "passive+no_connect"))
    )
    (net (code "373") (name "unconnected-(P10C-189-PadNC)") (class "Default")
      (node (ref "P10") (pin "NC") (pinfunction "189_NC") (pintype "passive+no_connect"))
    )
    (net (code "374") (name "unconnected-(P10C-194-PadNC)") (class "Default")
      (node (ref "P10") (pin "NC") (pinfunction "194_NC") (pintype "passive+no_connect"))
    )
    (net (code "375") (name "unconnected-(P10C-195-PadNC)") (class "Default")
      (node (ref "P10") (pin "NC") (pinfunction "195_NC") (pintype "passive+no_connect"))
    )
    (net (code "376") (name "unconnected-(P10C-196-PadNC)") (class "Default")
      (node (ref "P10") (pin "NC") (pinfunction "196_NC") (pintype "passive+no_connect"))
    )
    (net (code "377") (name "unconnected-(P10C-197-PadNC)") (class "Default")
      (node (ref "P10") (pin "NC") (pinfunction "197_NC") (pintype "passive+no_connect"))
    )
    (net (code "378") (name "unconnected-(P10C-200-PadNC)") (class "Default")
      (node (ref "P10") (pin "NC") (pinfunction "200_NC") (pintype "passive+no_connect"))
    )
    (net (code "379") (name "unconnected-(P10C-201-PadNC)") (class "Default")
      (node (ref "P10") (pin "NC") (pinfunction "201_NC") (pintype "passive+no_connect"))
    )
    (net (code "380") (name "unconnected-(P10C-202-PadNC)") (class "Default")
      (node (ref "P10") (pin "NC") (pinfunction "202_NC") (pintype "passive+no_connect"))
    )
    (net (code "381") (name "unconnected-(P10C-203-PadNC)") (class "Default")
      (node (ref "P10") (pin "NC") (pinfunction "203_NC") (pintype "passive+no_connect"))
    )
    (net (code "382") (name "unconnected-(P10C-216-PadNC)") (class "Default")
      (node (ref "P10") (pin "NC") (pinfunction "216_NC") (pintype "passive+no_connect"))
    )
    (net (code "383") (name "unconnected-(P10C-217-PadNC)") (class "Default")
      (node (ref "P10") (pin "NC") (pinfunction "217_NC") (pintype "passive+no_connect"))
    )
    (net (code "384") (name "unconnected-(P10C-218-PadNC)") (class "Default")
      (node (ref "P10") (pin "NC") (pinfunction "218_NC") (pintype "passive+no_connect"))
    )
    (net (code "385") (name "unconnected-(P10C-219-PadNC)") (class "Default")
      (node (ref "P10") (pin "NC") (pinfunction "219_NC") (pintype "passive+no_connect"))
    )
    (net (code "386") (name "unconnected-(P10C-221-PadNC)") (class "Default")
      (node (ref "P10") (pin "NC") (pinfunction "221_NC") (pintype "passive+no_connect"))
    )
    (net (code "387") (name "unconnected-(P10C-223-PadNC)") (class "Default")
      (node (ref "P10") (pin "NC") (pinfunction "223_NC") (pintype "passive+no_connect"))
    )
    (net (code "388") (name "unconnected-(SW-Pad3)") (class "Default")
      (node (ref "SW") (pin "3") (pinfunction "3_3") (pintype "passive+no_connect"))
    )
    (net (code "389") (name "unconnected-(U2-Pad4)") (class "Default")
      (node (ref "U2") (pin "4") (pinfunction "4_4") (pintype "passive+no_connect"))
    )
    (net (code "390") (name "unconnected-(U7-3.3V-Pad7)") (class "Default")
      (node (ref "U7") (pin "7") (pinfunction "3.3V_7") (pintype "passive"))
    )
    (net (code "391") (name "unconnected-(U7-5V-Pad9)") (class "Default")
      (node (ref "U7") (pin "9") (pinfunction "5V_9") (pintype "passive"))
    )
    (net (code "392") (name "unconnected-(U7-5V-Pad10)") (class "Default")
      (node (ref "U7") (pin "10") (pinfunction "5V_10") (pintype "passive"))
    )
    (net (code "393") (name "unconnected-(U7-GND-Pad5)") (class "Default")
      (node (ref "U7") (pin "5") (pinfunction "GND_5") (pintype "passive"))
    )
    (net (code "394") (name "unconnected-(U7-RST-Pad1)") (class "Default")
      (node (ref "U7") (pin "1") (pinfunction "RST_1") (pintype "passive"))
    )
    (net (code "395") (name "unconnected-(U7-SWIM-Pad3)") (class "Default")
      (node (ref "U7") (pin "3") (pinfunction "SWIM_3") (pintype "passive"))
    )
    (net (code "396") (name "unconnected-(U13-PC14-OSC32_IN-Pad8)") (class "Default")
      (node (ref "U13") (pin "8") (pinfunction "PC14-OSC32_IN_8") (pintype "passive"))
    )
    (net (code "397") (name "unconnected-(U13-PC15-OSC32_OUT-Pad9)") (class "Default")
      (node (ref "U13") (pin "9") (pinfunction "PC15-OSC32_OUT_9") (pintype "passive"))
    )
  )
)
